# Doppler_LED_Controller.net
KiCad netlist of a schematic drawn in EAGLE
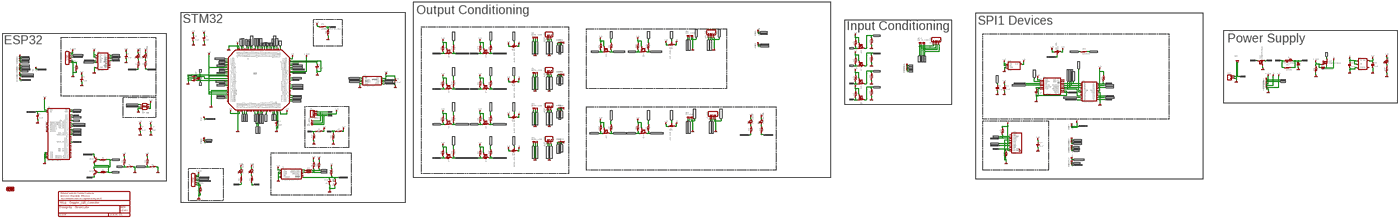
[diagram p0: schematic, sheet 1, overview]
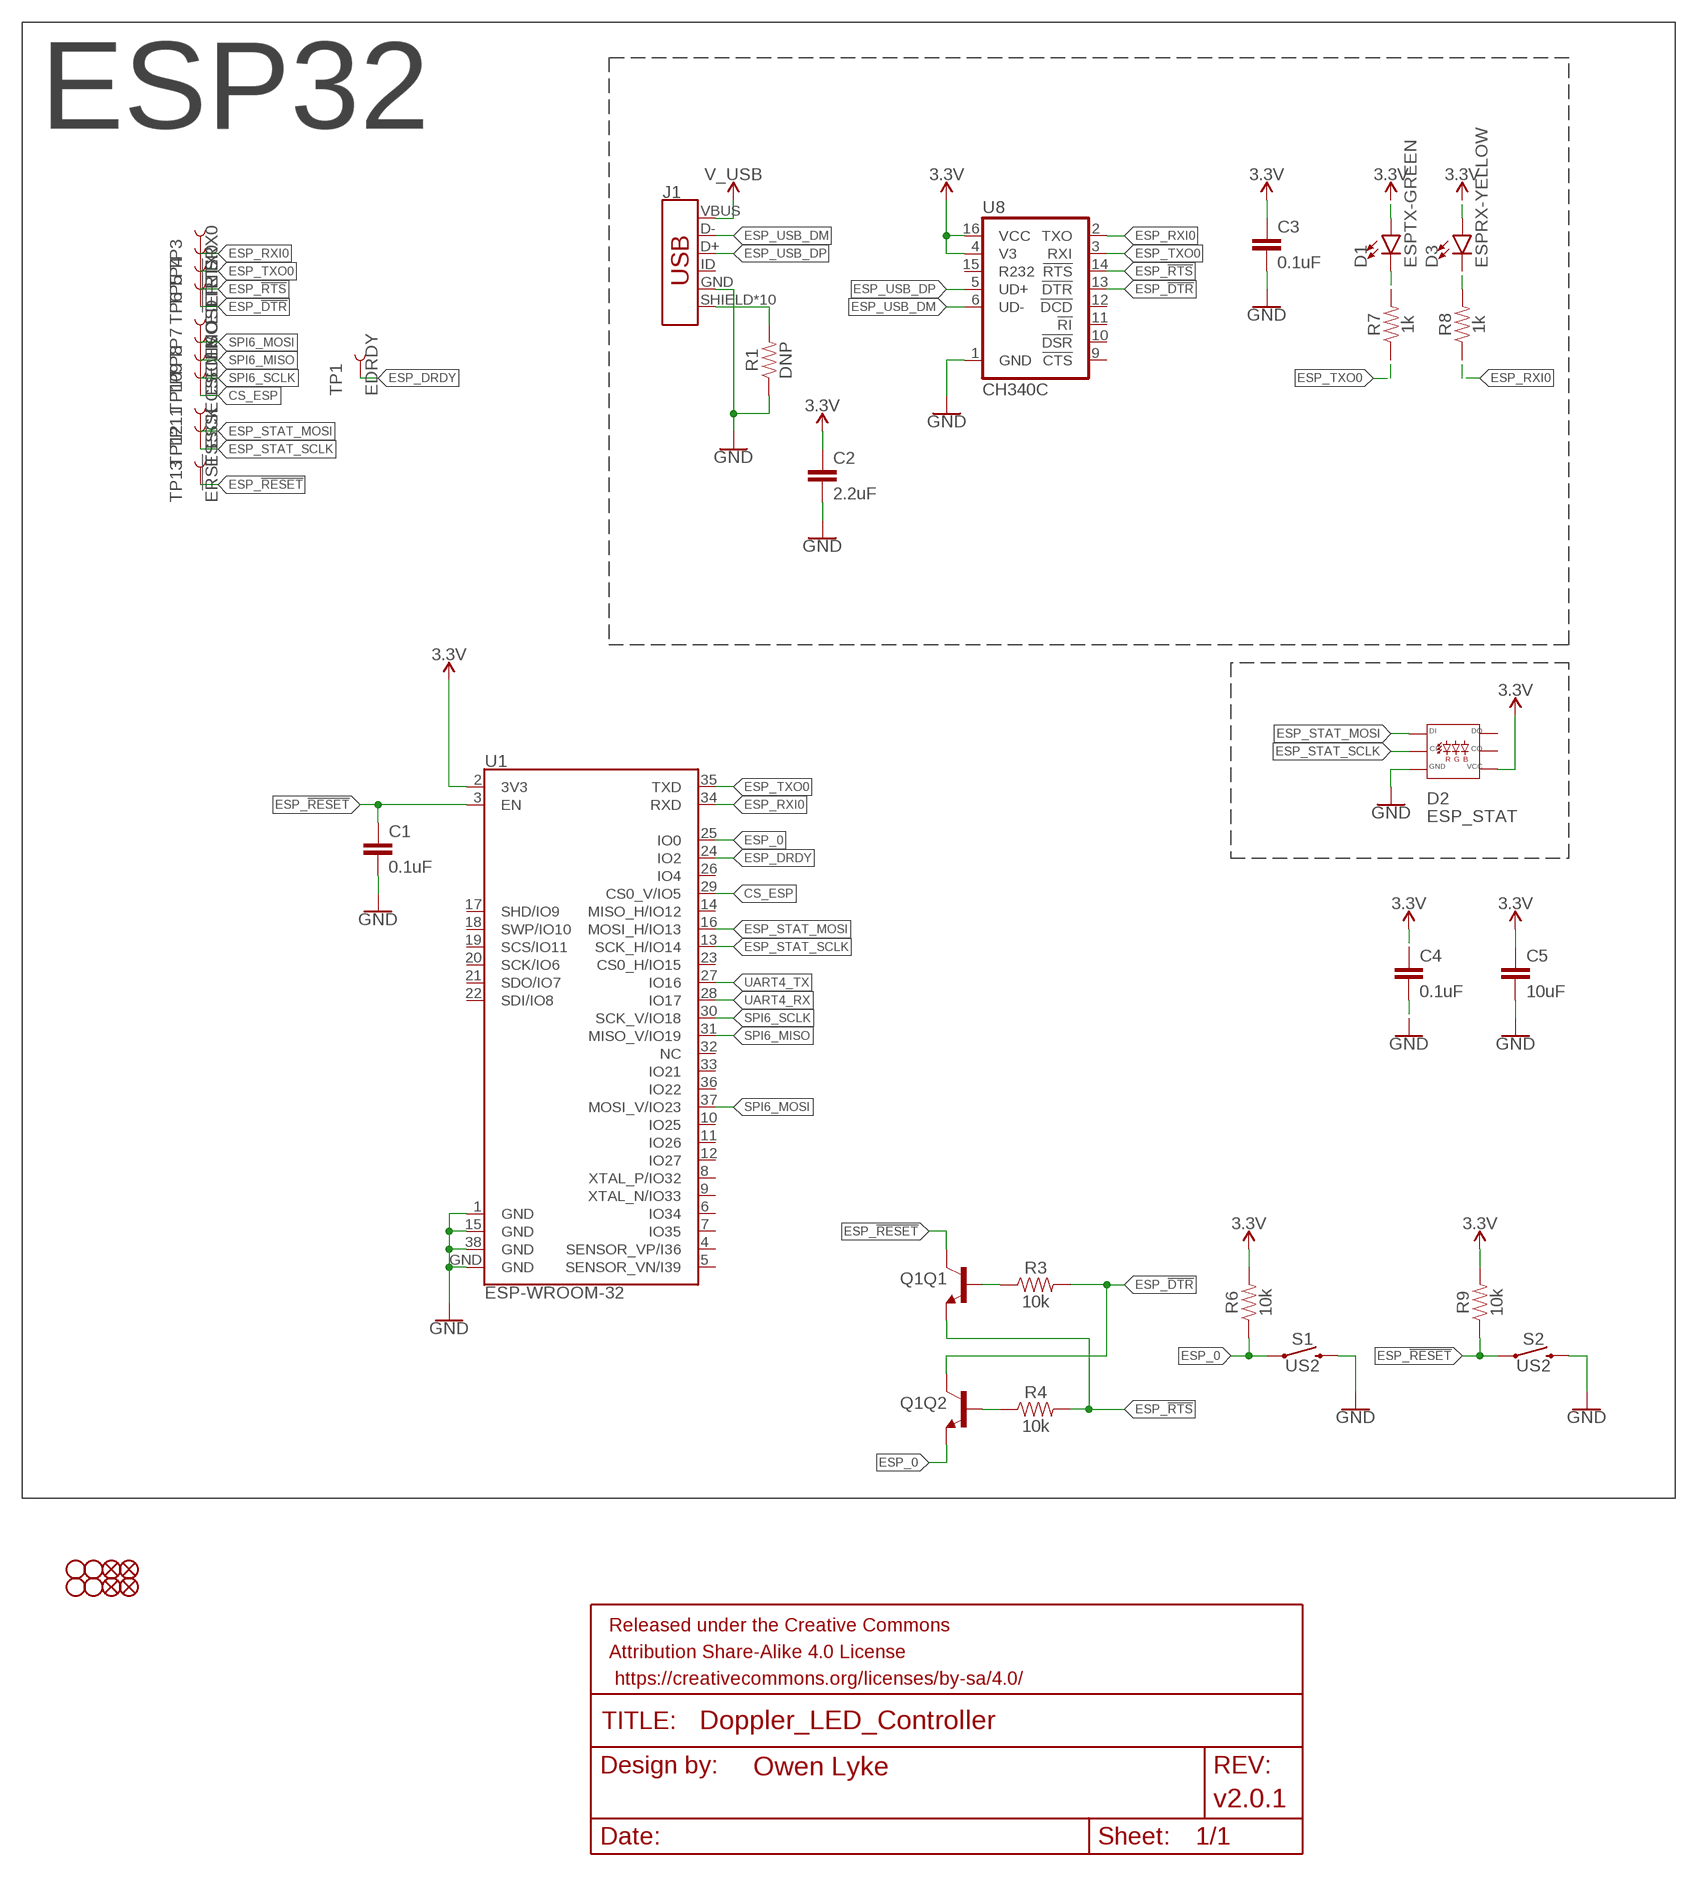
[diagram p1: schematic, sheet 1, part 1 of 6]
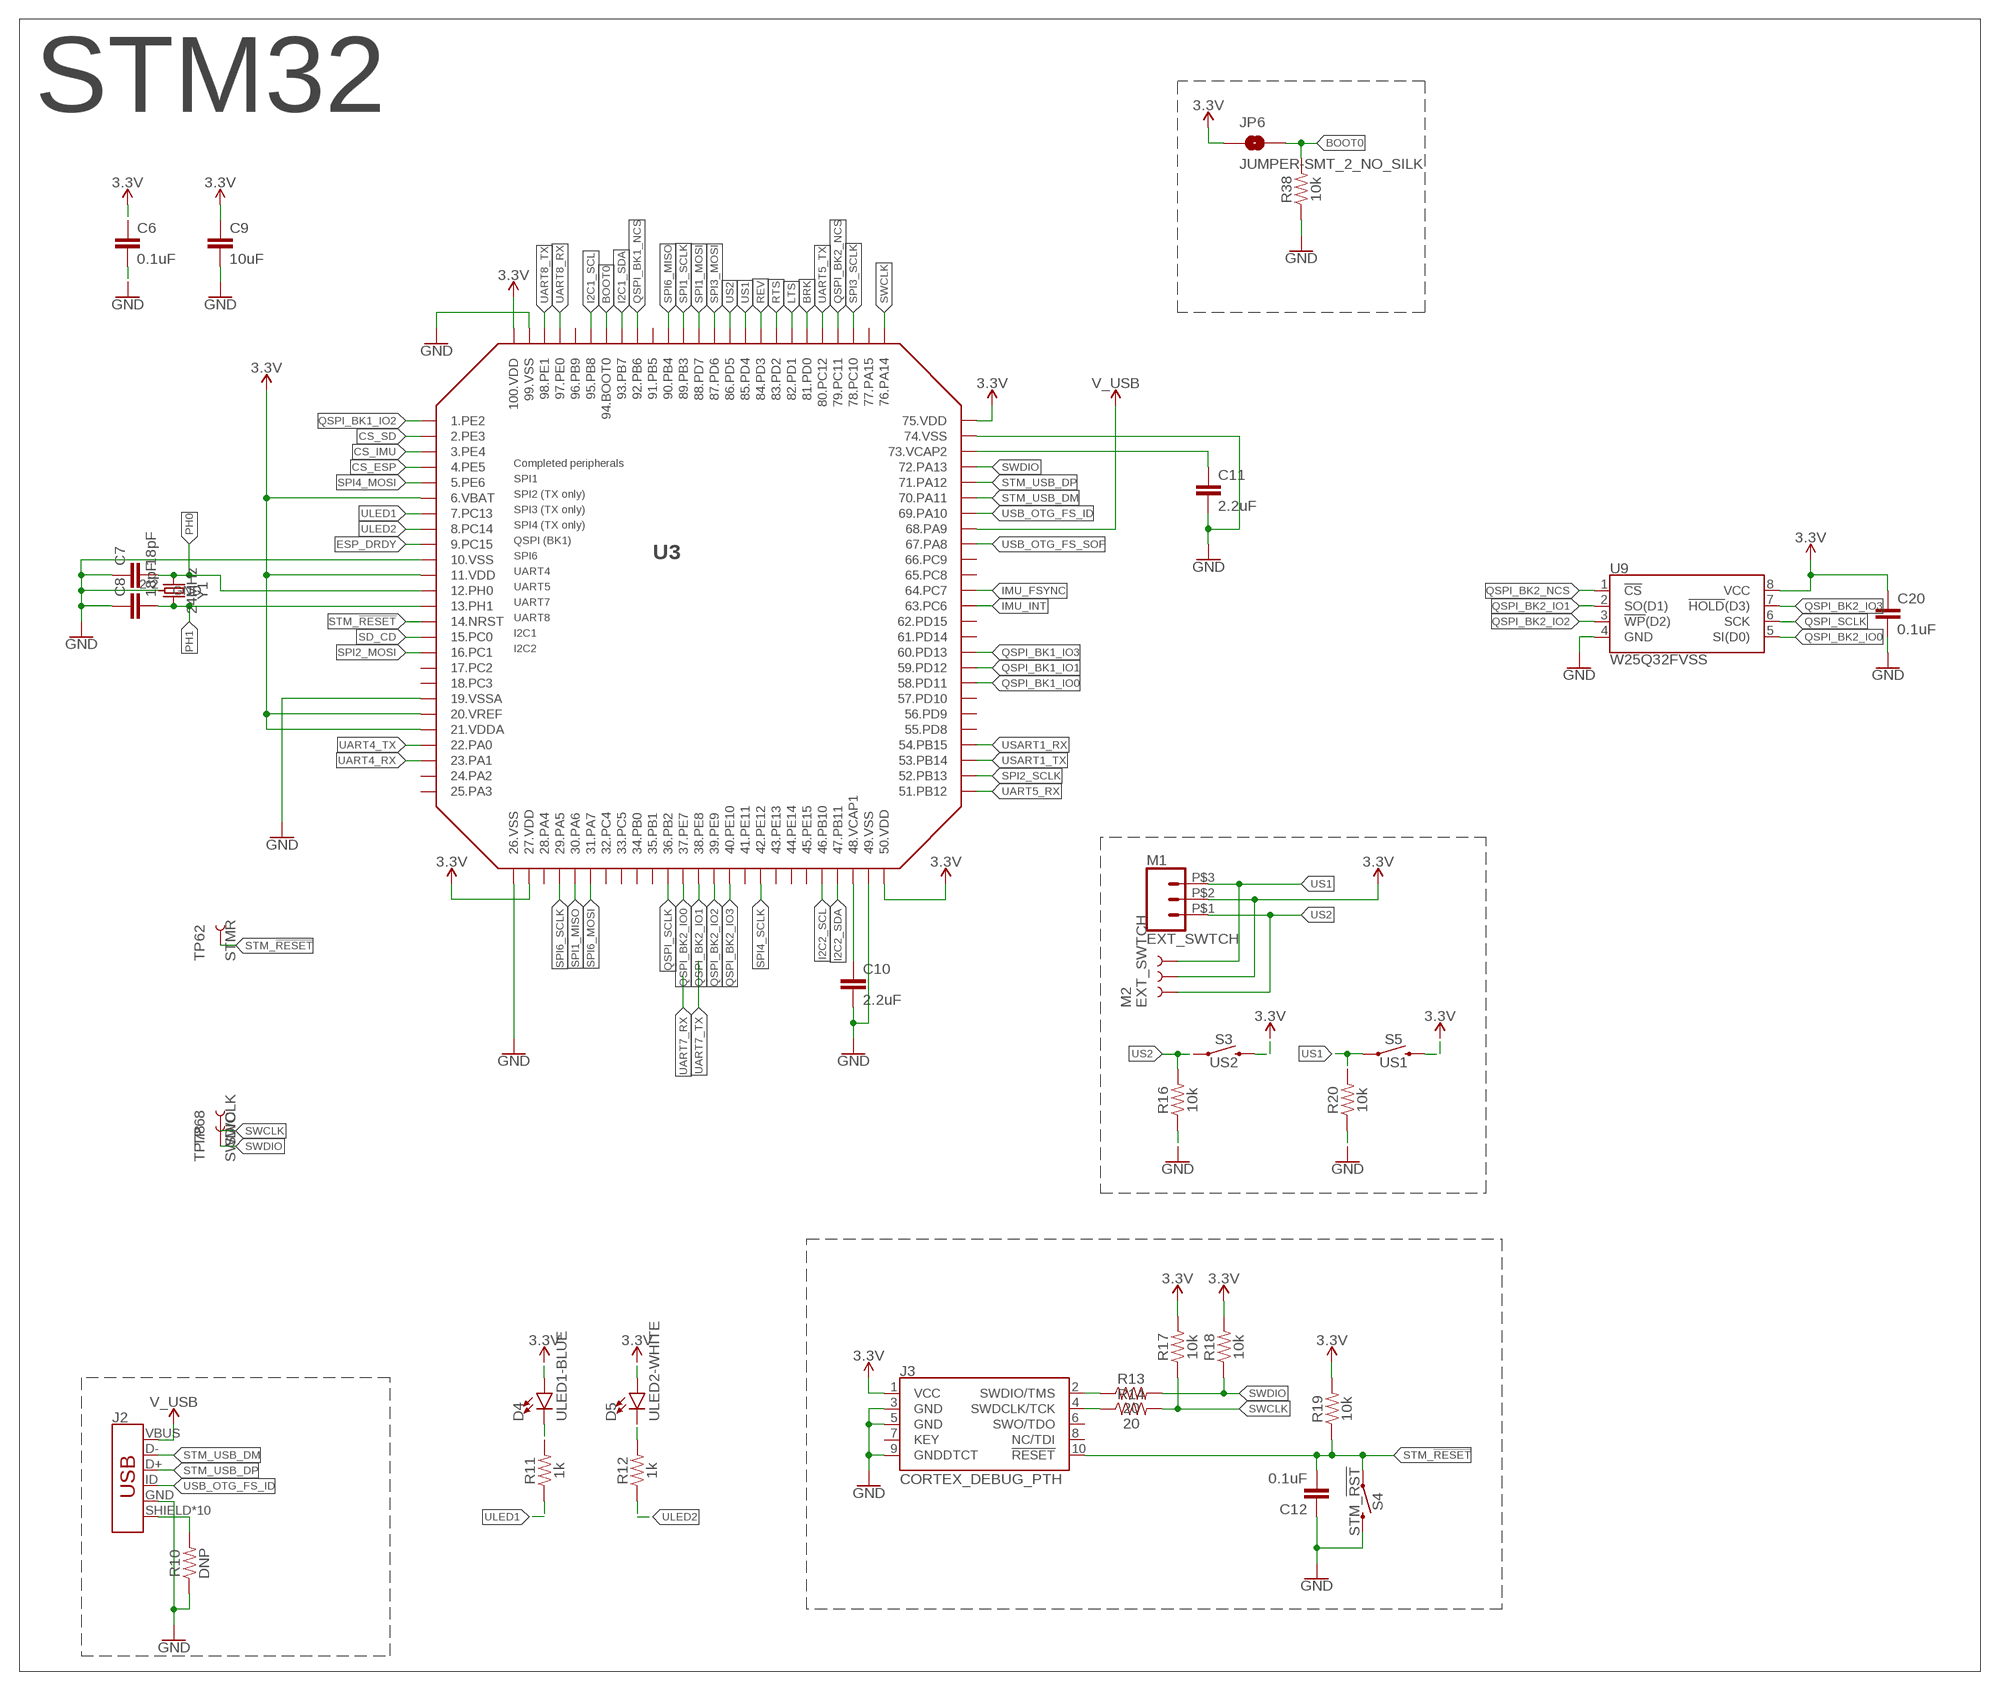
[diagram p2: schematic, sheet 1, part 2 of 6]
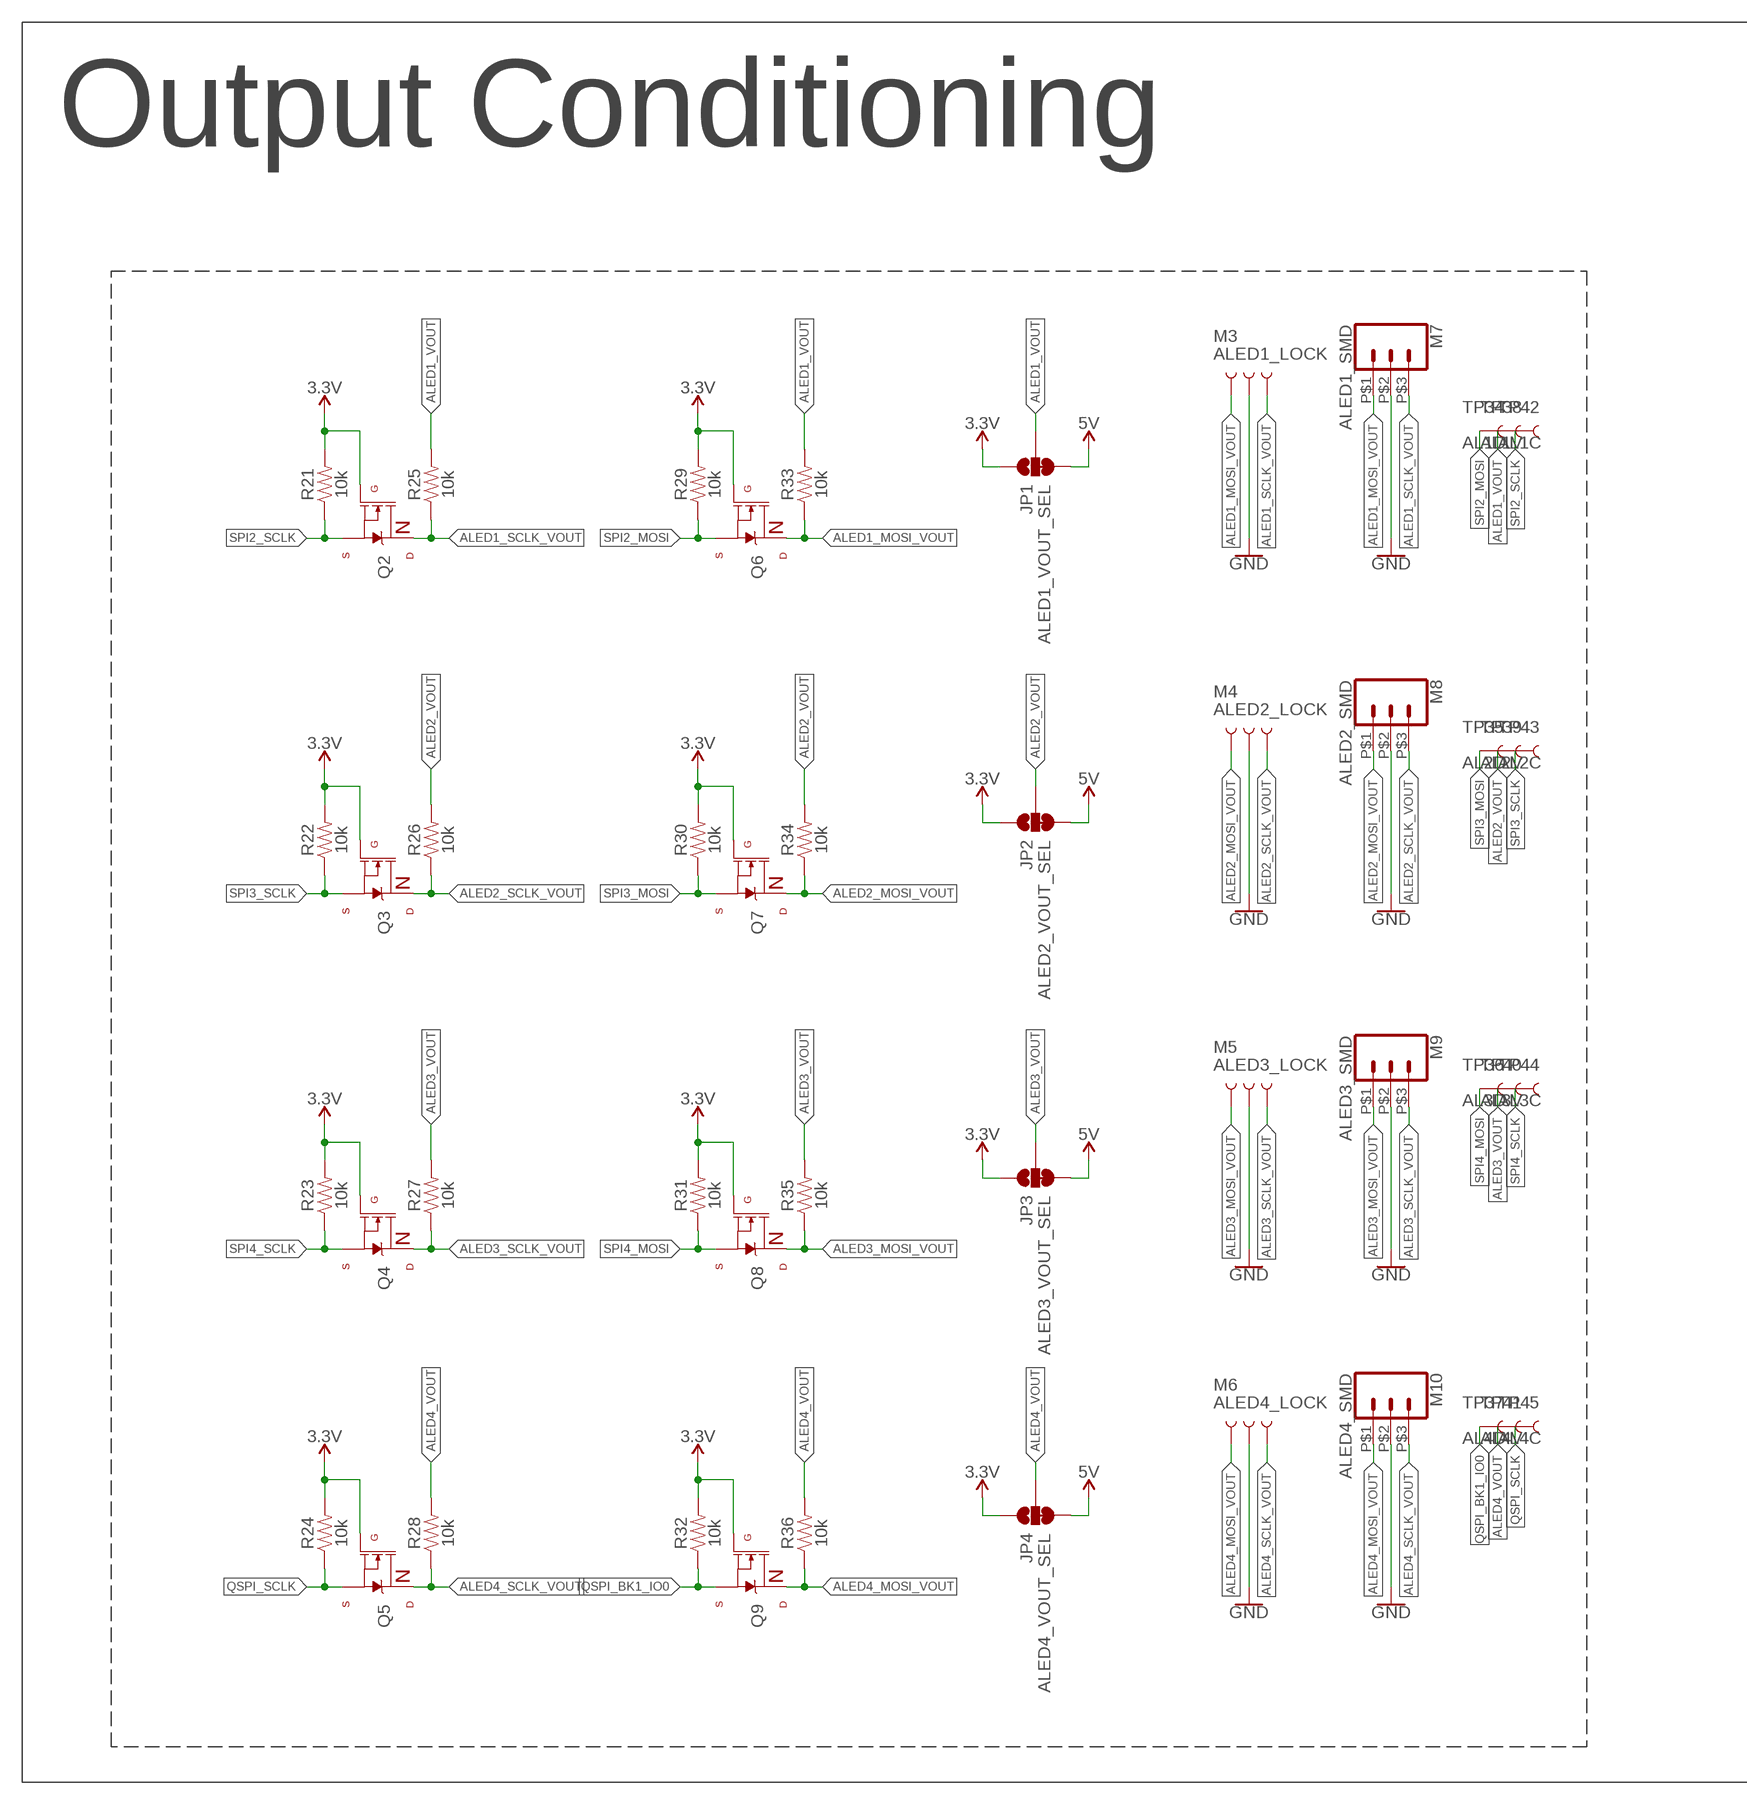
[diagram p3: schematic, sheet 1, part 3 of 6]
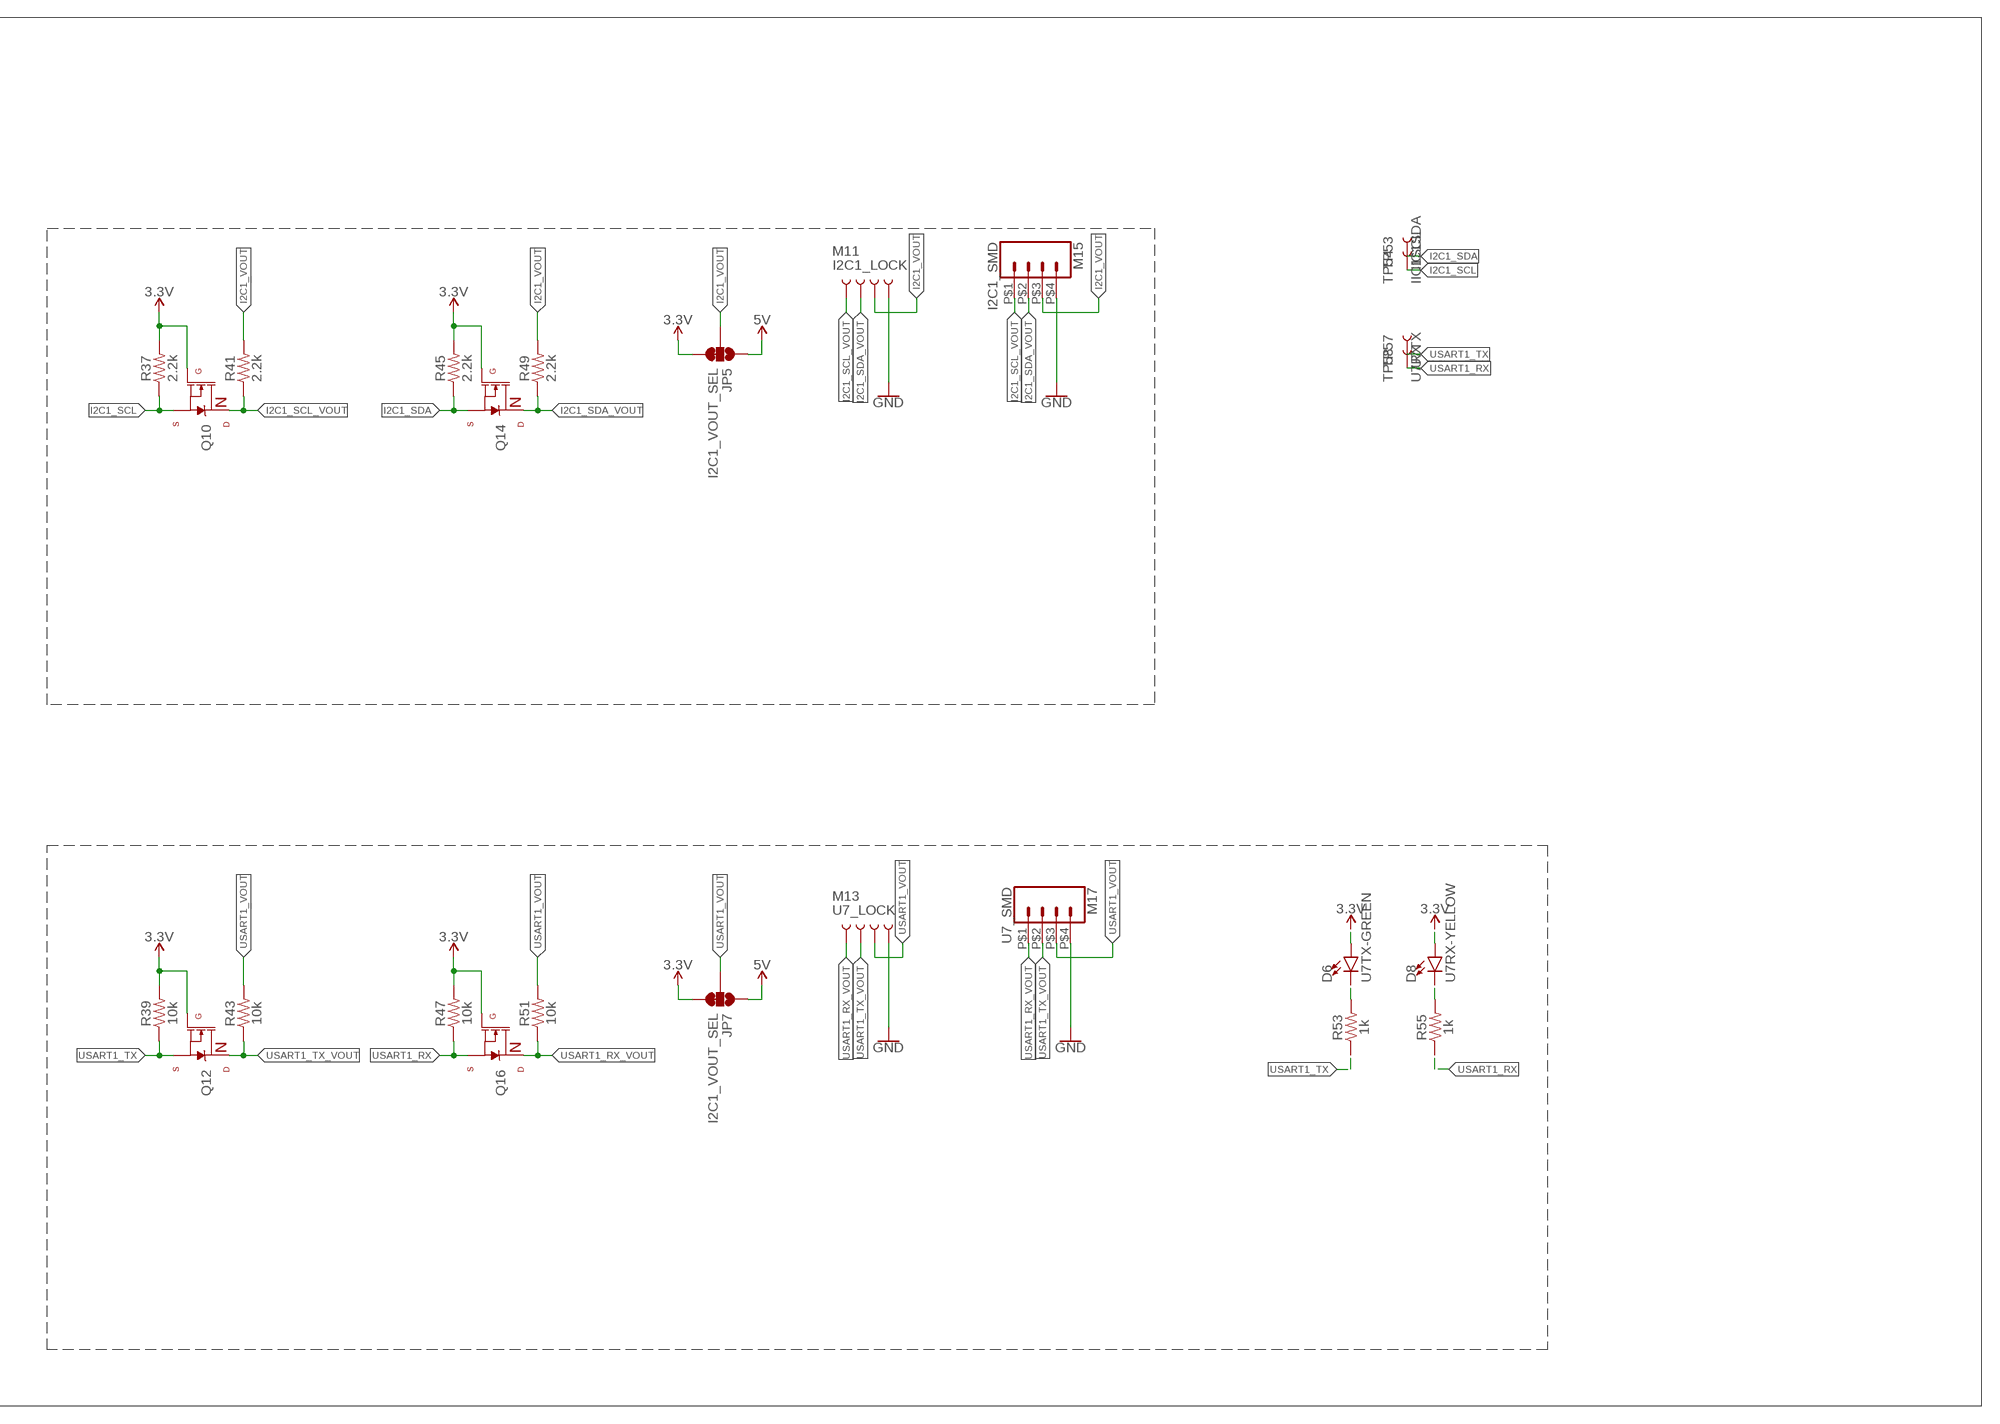
[diagram p4: schematic, sheet 1, part 4 of 6]
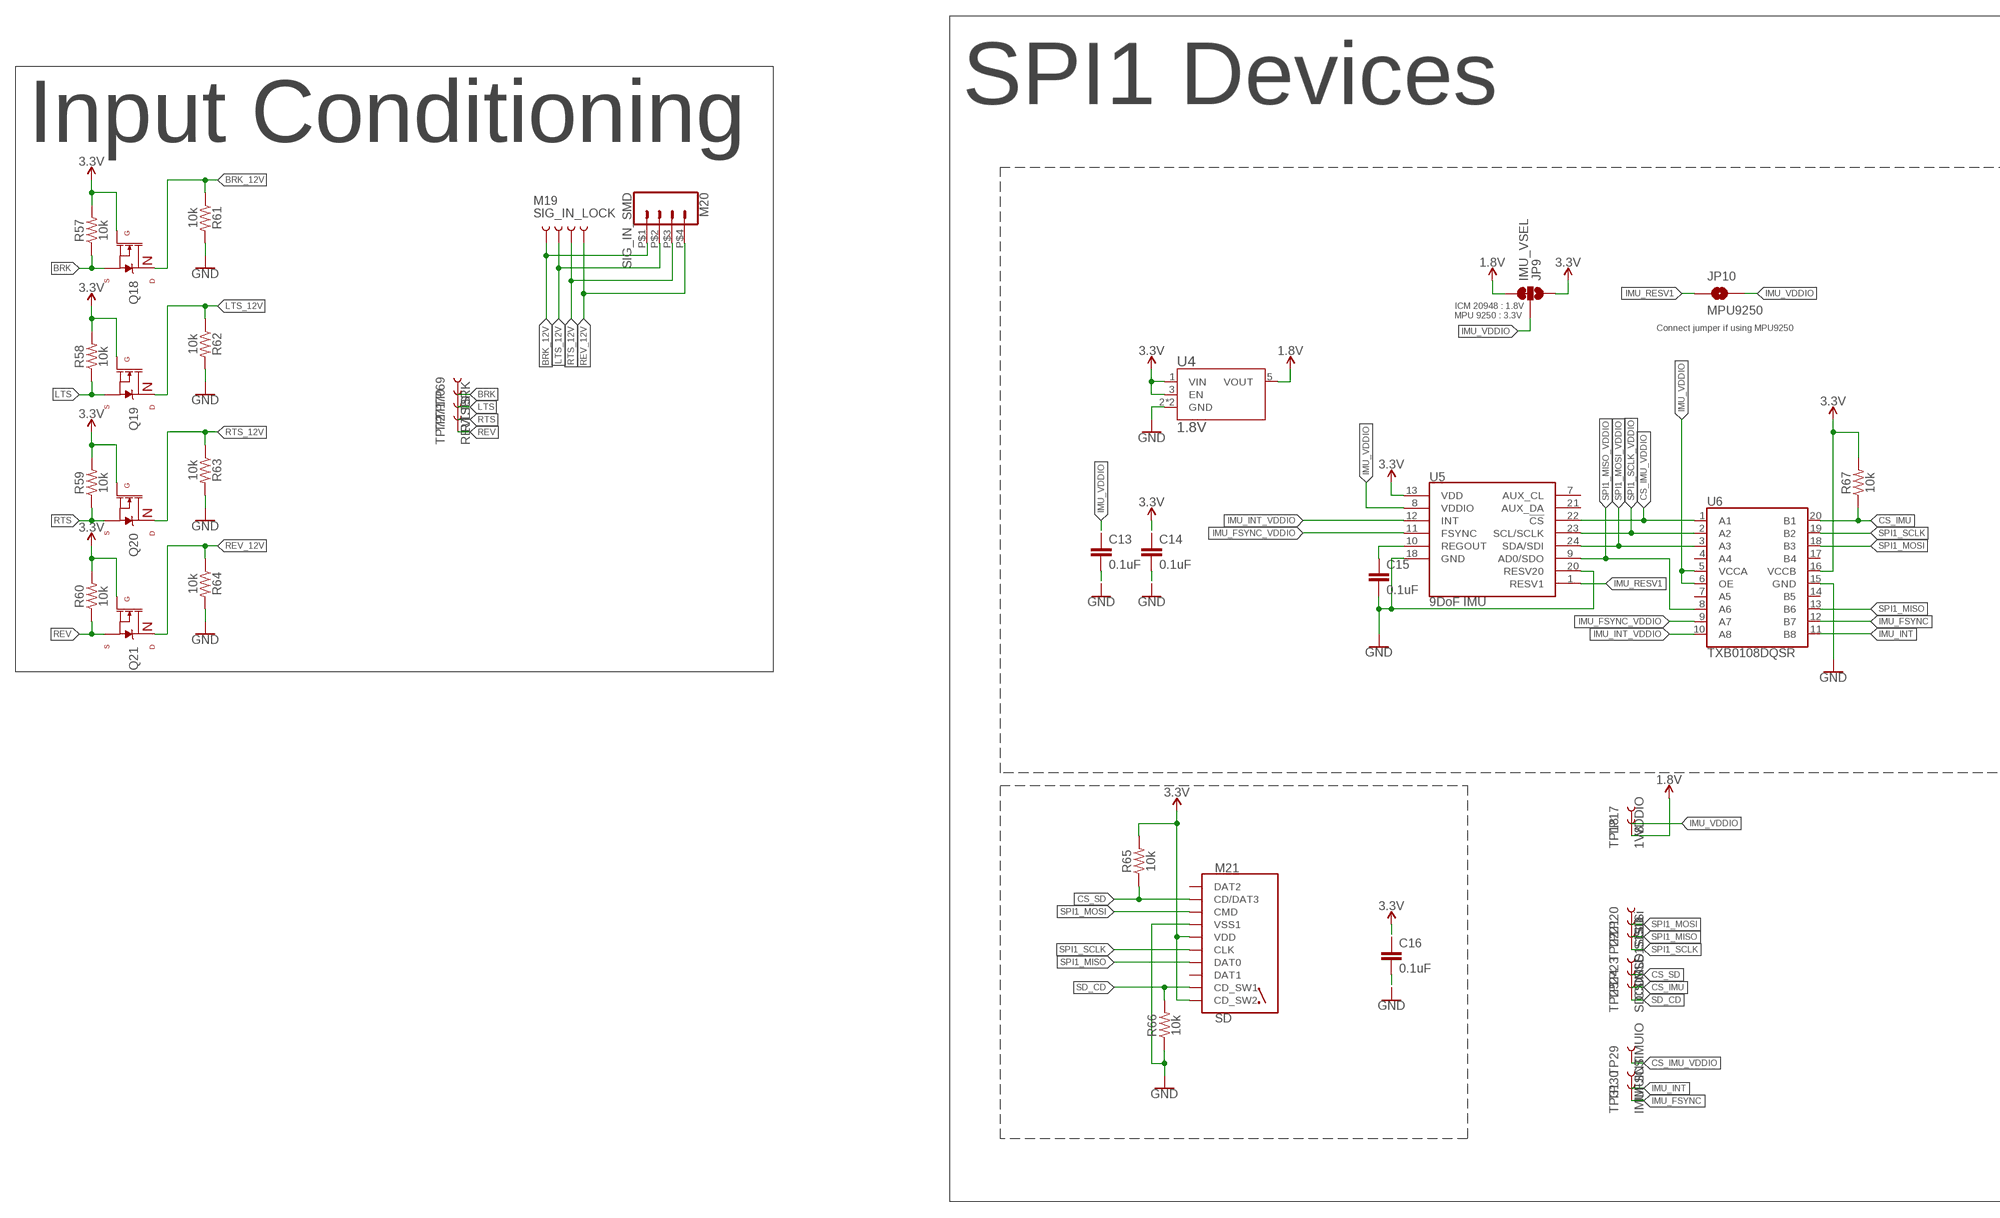
[diagram p5: schematic, sheet 1, part 5 of 6]
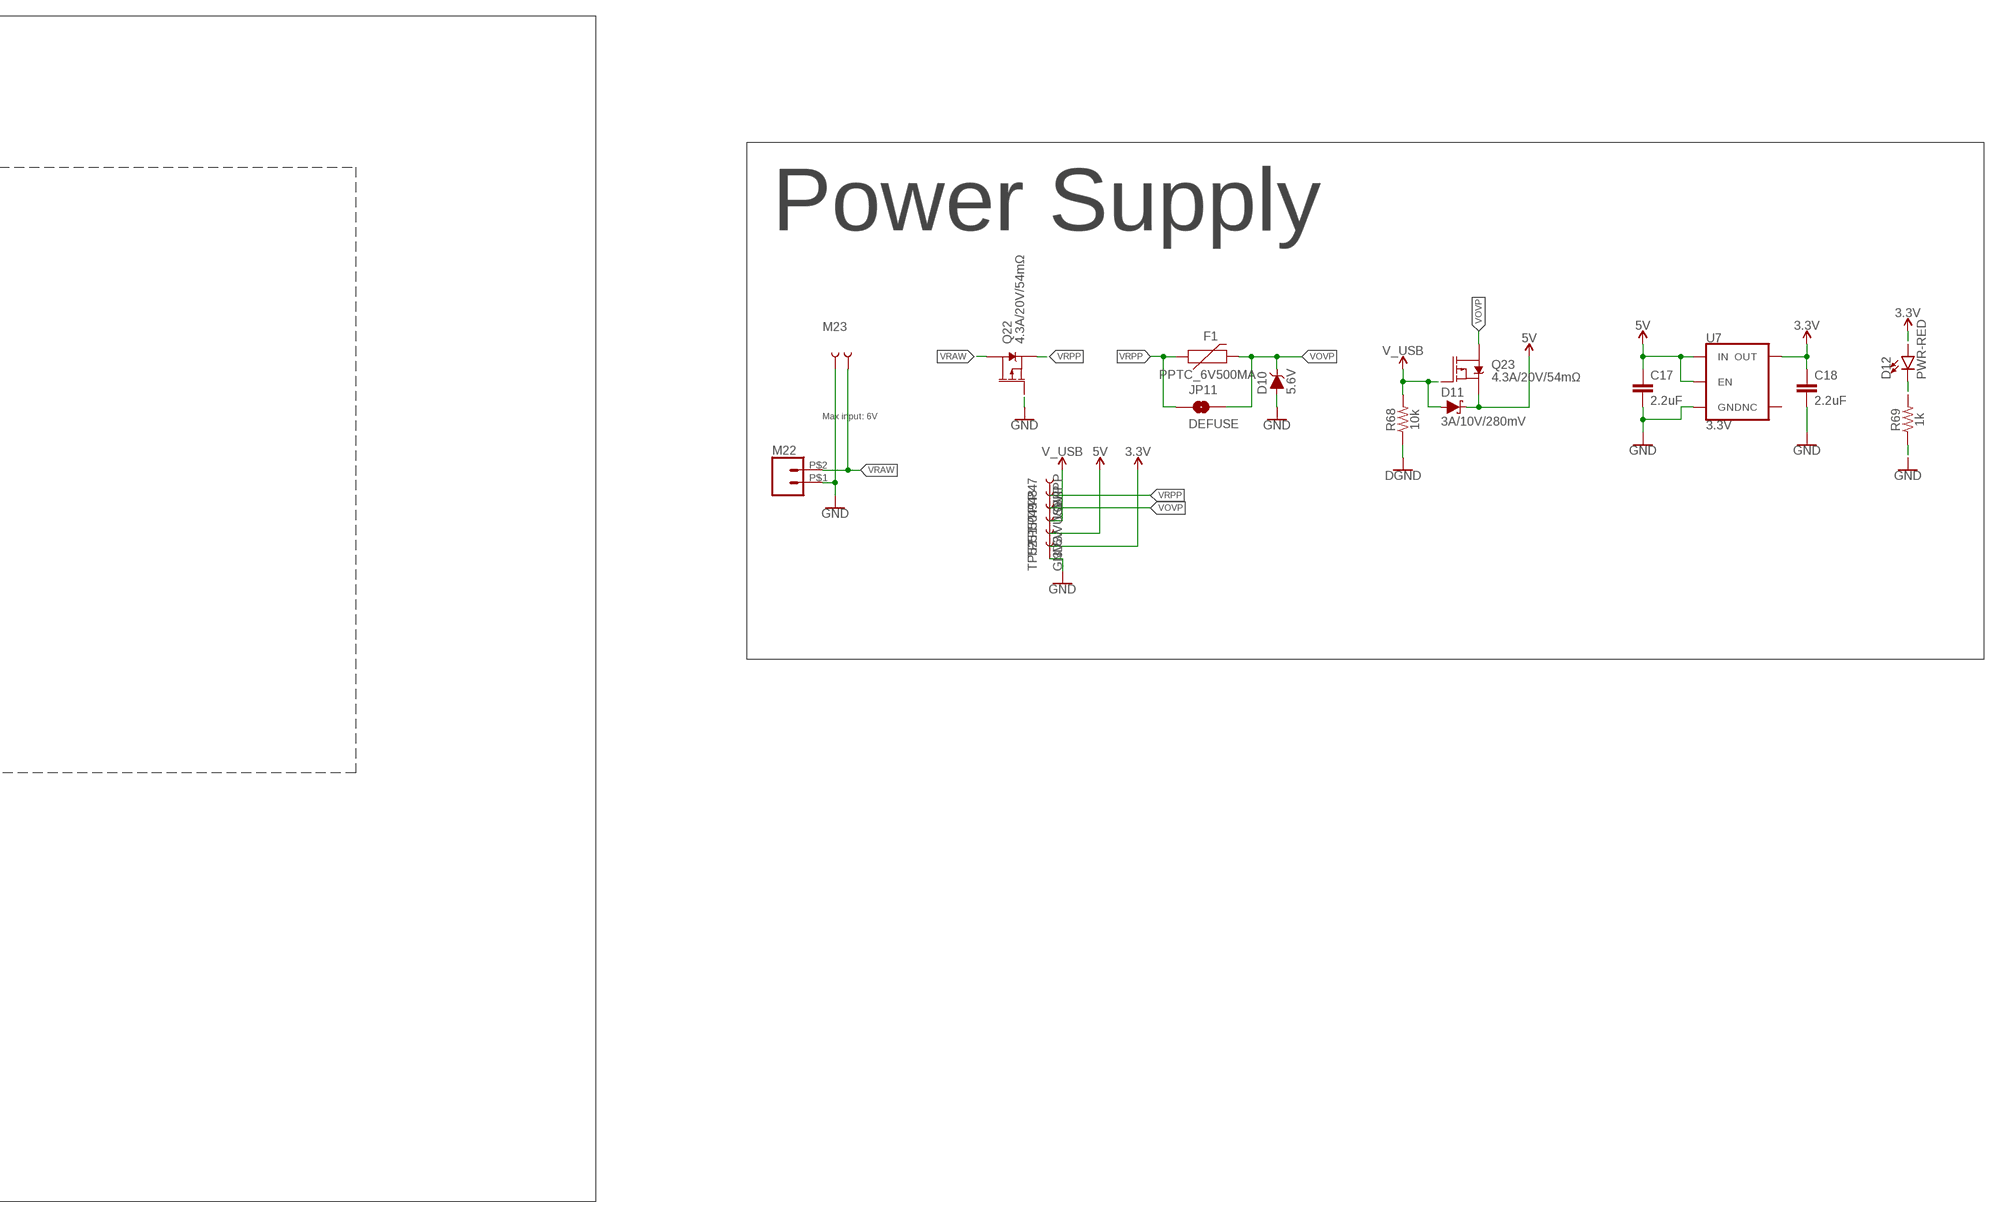
[diagram p6: schematic, sheet 1, part 6 of 6]

(export (version "E")
  (design (tool "Eeschema 10.0.6"))
  (components
    (comp (ref "C1")
      (value "0.1uF")
      (footprint "eagle-import:0603")
      (libsource (lib "eagle-import") (part "0.1UF-0603-25V-5%"))
    )
    (comp (ref "C2")
      (value "2.2uF")
      (footprint "eagle-import:0603")
      (libsource (lib "eagle-import") (part "2.2UF-0603-10V-20%"))
    )
    (comp (ref "C3")
      (value "0.1uF")
      (footprint "eagle-import:0603")
      (libsource (lib "eagle-import") (part "0.1UF-0603-25V-5%"))
    )
    (comp (ref "C4")
      (value "0.1uF")
      (footprint "eagle-import:0603")
      (libsource (lib "eagle-import") (part "0.1UF-0603-25V-5%"))
    )
    (comp (ref "C5")
      (value "10uF")
      (footprint "eagle-import:0603")
      (libsource (lib "eagle-import") (part "10UF-0603-6.3V-20%"))
    )
    (comp (ref "C6")
      (value "0.1uF")
      (footprint "eagle-import:0603")
      (libsource (lib "eagle-import") (part "0.1UF-0603-25V-5%"))
    )
    (comp (ref "C7")
      (value "18pF")
      (footprint "eagle-import:0603")
      (libsource (lib "eagle-import") (part "18PF-0603-50V-5%"))
    )
    (comp (ref "C8")
      (value "18pF")
      (footprint "eagle-import:0603")
      (libsource (lib "eagle-import") (part "18PF-0603-50V-5%"))
    )
    (comp (ref "C9")
      (value "10uF")
      (footprint "eagle-import:0603")
      (libsource (lib "eagle-import") (part "10UF-0603-6.3V-20%"))
    )
    (comp (ref "C10")
      (value "2.2uF")
      (footprint "eagle-import:0603")
      (libsource (lib "eagle-import") (part "2.2UF-0603-10V-20%"))
    )
    (comp (ref "C11")
      (value "2.2uF")
      (footprint "eagle-import:0603")
      (libsource (lib "eagle-import") (part "2.2UF-0603-10V-20%"))
    )
    (comp (ref "C12")
      (value "0.1uF")
      (footprint "eagle-import:0603")
      (libsource (lib "eagle-import") (part "0.1UF-0603-25V-5%"))
    )
    (comp (ref "C13")
      (value "0.1uF")
      (footprint "eagle-import:0603")
      (libsource (lib "eagle-import") (part "0.1UF-0603-25V-5%"))
    )
    (comp (ref "C14")
      (value "0.1uF")
      (footprint "eagle-import:0603")
      (libsource (lib "eagle-import") (part "0.1UF-0603-25V-5%"))
    )
    (comp (ref "C15")
      (value "0.1uF")
      (footprint "eagle-import:0603")
      (libsource (lib "eagle-import") (part "0.1UF-0603-25V-5%"))
    )
    (comp (ref "C16")
      (value "0.1uF")
      (footprint "eagle-import:0603")
      (libsource (lib "eagle-import") (part "0.1UF-0603-25V-5%"))
    )
    (comp (ref "C17")
      (value "2.2uF")
      (footprint "eagle-import:0603")
      (libsource (lib "eagle-import") (part "2.2UF-0603-10V-20%"))
    )
    (comp (ref "C18")
      (value "2.2uF")
      (footprint "eagle-import:0603")
      (libsource (lib "eagle-import") (part "2.2UF-0603-10V-20%"))
    )
    (comp (ref "C20")
      (value "0.1uF")
      (footprint "eagle-import:0603")
      (libsource (lib "eagle-import") (part "0.1UF-0603-25V-(+80/-20%)"))
    )
    (comp (ref "D1")
      (value "ESPTX-GREEN")
      (footprint "eagle-import:LED-0603")
      (libsource (lib "eagle-import") (part "LED-GREEN0603"))
    )
    (comp (ref "D2")
      (value "ESP_STAT")
      (footprint "eagle-import:APA102_2020_LONG")
      (libsource (lib "eagle-import") (part "APA1022020_LONG"))
    )
    (comp (ref "D3")
      (value "ESPRX-YELLOW")
      (footprint "eagle-import:LED-0603")
      (libsource (lib "eagle-import") (part "LED-YELLOW0603"))
    )
    (comp (ref "D4")
      (value "ULED1-BLUE")
      (footprint "eagle-import:LED-0603")
      (libsource (lib "eagle-import") (part "LED-BLUE0603"))
    )
    (comp (ref "D5")
      (value "ULED2-WHITE")
      (footprint "eagle-import:LED-0603")
      (libsource (lib "eagle-import") (part "LED-WHITE0603"))
    )
    (comp (ref "D6")
      (value "U7TX-GREEN")
      (footprint "eagle-import:LED-0603")
      (libsource (lib "eagle-import") (part "LED-GREEN0603"))
    )
    (comp (ref "D8")
      (value "U7RX-YELLOW")
      (footprint "eagle-import:LED-0603")
      (libsource (lib "eagle-import") (part "LED-YELLOW0603"))
    )
    (comp (ref "D10")
      (value "5.6V")
      (footprint "eagle-import:SOD-323")
      (libsource (lib "eagle-import") (part "DIODE-ZENER-MMSZ5232BS"))
    )
    (comp (ref "D11")
      (value "3A/10V/280mV")
      (footprint "eagle-import:SOD-323")
      (libsource (lib "eagle-import") (part "DIODE-SCHOTTKY-BAT60A"))
    )
    (comp (ref "D12")
      (value "PWR-RED")
      (footprint "eagle-import:LED-0603")
      (libsource (lib "eagle-import") (part "LED-RED0603"))
    )
    (comp (ref "F1")
      (value "PPTC_6V500MA")
      (footprint "eagle-import:0805")
      (libsource (lib "eagle-import") (part "PPTC_6V500MA"))
    )
    (comp (ref "FD1")
      (value "FIDUCIAL1X2")
      (footprint "eagle-import:FIDUCIAL-1X2")
      (libsource (lib "eagle-import") (part "FIDUCIAL1X2"))
    )
    (comp (ref "FD2")
      (value "FIDUCIAL1X2")
      (footprint "eagle-import:FIDUCIAL-1X2")
      (libsource (lib "eagle-import") (part "FIDUCIAL1X2"))
    )
    (comp (ref "FD3")
      (value "FIDUCIAL1X2")
      (footprint "eagle-import:FIDUCIAL-1X2")
      (libsource (lib "eagle-import") (part "FIDUCIAL1X2"))
    )
    (comp (ref "FD4")
      (value "FIDUCIAL1X2")
      (footprint "eagle-import:FIDUCIAL-1X2")
      (libsource (lib "eagle-import") (part "FIDUCIAL1X2"))
    )
    (comp (ref "H1")
      (value "STAND-OFF")
      (footprint "eagle-import:STAND-OFF")
      (libsource (lib "eagle-import") (part "STAND-OFF"))
    )
    (comp (ref "H2")
      (value "STAND-OFF")
      (footprint "eagle-import:STAND-OFF")
      (libsource (lib "eagle-import") (part "STAND-OFF"))
    )
    (comp (ref "H3")
      (value "STAND-OFF")
      (footprint "eagle-import:STAND-OFF")
      (libsource (lib "eagle-import") (part "STAND-OFF"))
    )
    (comp (ref "H4")
      (value "STAND-OFF")
      (footprint "eagle-import:STAND-OFF")
      (libsource (lib "eagle-import") (part "STAND-OFF"))
    )
    (comp (ref "J1")
      (value "USB_MICRO-B_HALF_PTH_MILL")
      (footprint "eagle-import:USB-MICROB-PTH-MILL")
      (libsource (lib "eagle-import") (part "USB_MICRO-B_HALF_PTH_MILL"))
    )
    (comp (ref "J2")
      (value "USB_MICRO-B_HALF_PTH_MILL")
      (footprint "eagle-import:USB-MICROB-PTH-MILL")
      (libsource (lib "eagle-import") (part "USB_MICRO-B_HALF_PTH_MILL"))
    )
    (comp (ref "J3")
      (value "CORTEX_DEBUG_PTH")
      (footprint "eagle-import:2X5-PTH-1.27MM")
      (libsource (lib "eagle-import") (part "CORTEX_DEBUG_PTH"))
    )
    (comp (ref "JP1")
      (value "ALED1_VOUT_SEL")
      (footprint "eagle-import:SMT-JUMPER_3_1-NC_TRACE_SILK")
      (libsource (lib "eagle-import") (part "JUMPER-SMT_3_1-NC_TRACE_SILK"))
    )
    (comp (ref "JP2")
      (value "ALED2_VOUT_SEL")
      (footprint "eagle-import:SMT-JUMPER_3_1-NC_TRACE_SILK")
      (libsource (lib "eagle-import") (part "JUMPER-SMT_3_1-NC_TRACE_SILK"))
    )
    (comp (ref "JP3")
      (value "ALED3_VOUT_SEL")
      (footprint "eagle-import:SMT-JUMPER_3_1-NC_TRACE_SILK")
      (libsource (lib "eagle-import") (part "JUMPER-SMT_3_1-NC_TRACE_SILK"))
    )
    (comp (ref "JP4")
      (value "ALED4_VOUT_SEL")
      (footprint "eagle-import:SMT-JUMPER_3_1-NC_TRACE_SILK")
      (libsource (lib "eagle-import") (part "JUMPER-SMT_3_1-NC_TRACE_SILK"))
    )
    (comp (ref "JP5")
      (value "I2C1_VOUT_SEL")
      (footprint "eagle-import:SMT-JUMPER_3_1-NC_TRACE_SILK")
      (libsource (lib "eagle-import") (part "JUMPER-SMT_3_1-NC_TRACE_SILK"))
    )
    (comp (ref "JP6")
      (value "JUMPER-SMT_2_NO_SILK")
      (footprint "eagle-import:SMT-JUMPER_2_NO_SILK")
      (libsource (lib "eagle-import") (part "JUMPER-SMT_2_NO_SILK"))
    )
    (comp (ref "JP7")
      (value "I2C1_VOUT_SEL")
      (footprint "eagle-import:SMT-JUMPER_3_1-NC_TRACE_SILK")
      (libsource (lib "eagle-import") (part "JUMPER-SMT_3_1-NC_TRACE_SILK"))
    )
    (comp (ref "JP9")
      (value "IMU_VSEL")
      (footprint "eagle-import:SMT-JUMPER_3_1-NC_TRACE_SILK")
      (libsource (lib "eagle-import") (part "JUMPER-SMT_3_1-NC_TRACE_SILK"))
    )
    (comp (ref "JP10")
      (value "MPU9250")
      (footprint "eagle-import:SMT-JUMPER_2_NO_SILK")
      (libsource (lib "eagle-import") (part "JUMPER-SMT_2_NO_SILK"))
    )
    (comp (ref "JP11")
      (value "DEFUSE")
      (footprint "eagle-import:SMT-JUMPER_2_NO_SILK")
      (libsource (lib "eagle-import") (part "JUMPER-SMT_2_NO_SILK"))
    )
    (comp (ref "M1")
      (value "EXT_SWTCH")
      (footprint "eagle-import:1X03_SMD_0.1IN")
      (libsource (lib "eagle-import") (part "CONN_SMD_3"))
    )
    (comp (ref "M2")
      (value "EXT_SWTCH")
      (footprint "eagle-import:3_PIN_LOCK")
      (libsource (lib "eagle-import") (part "CONN_LED_OUT-MOLEX_5055670371"))
    )
    (comp (ref "M3")
      (value "ALED1_LOCK")
      (footprint "eagle-import:3_PIN_LOCK")
      (libsource (lib "eagle-import") (part "CONN_LED_OUT-MOLEX_5055670371"))
    )
    (comp (ref "M4")
      (value "ALED2_LOCK")
      (footprint "eagle-import:3_PIN_LOCK")
      (libsource (lib "eagle-import") (part "CONN_LED_OUT-MOLEX_5055670371"))
    )
    (comp (ref "M5")
      (value "ALED3_LOCK")
      (footprint "eagle-import:3_PIN_LOCK")
      (libsource (lib "eagle-import") (part "CONN_LED_OUT-MOLEX_5055670371"))
    )
    (comp (ref "M6")
      (value "ALED4_LOCK")
      (footprint "eagle-import:3_PIN_LOCK")
      (libsource (lib "eagle-import") (part "CONN_LED_OUT-MOLEX_5055670371"))
    )
    (comp (ref "M7")
      (value "ALED1_SMD")
      (footprint "eagle-import:1X03_SMD_0.1IN")
      (libsource (lib "eagle-import") (part "CONN_SMD_3"))
    )
    (comp (ref "M8")
      (value "ALED2_SMD")
      (footprint "eagle-import:1X03_SMD_0.1IN")
      (libsource (lib "eagle-import") (part "CONN_SMD_3"))
    )
    (comp (ref "M9")
      (value "ALED3_SMD")
      (footprint "eagle-import:1X03_SMD_0.1IN")
      (libsource (lib "eagle-import") (part "CONN_SMD_3"))
    )
    (comp (ref "M10")
      (value "ALED4_SMD")
      (footprint "eagle-import:1X03_SMD_0.1IN")
      (libsource (lib "eagle-import") (part "CONN_SMD_3"))
    )
    (comp (ref "M11")
      (value "I2C1_LOCK")
      (footprint "eagle-import:4_PIN_LOCK")
      (libsource (lib "eagle-import") (part "CONN_LOCK_4-MOLEX_5055670471"))
    )
    (comp (ref "M13")
      (value "U7_LOCK")
      (footprint "eagle-import:4_PIN_LOCK")
      (libsource (lib "eagle-import") (part "CONN_LOCK_4-MOLEX_5055670471"))
    )
    (comp (ref "M15")
      (value "I2C1_SMD")
      (footprint "eagle-import:1X04_SMD_0.1IN")
      (libsource (lib "eagle-import") (part "CONN_SMD_4"))
    )
    (comp (ref "M17")
      (value "U7_SMD")
      (footprint "eagle-import:1X04_SMD_0.1IN")
      (libsource (lib "eagle-import") (part "CONN_SMD_4"))
    )
    (comp (ref "M19")
      (value "SIG_IN_LOCK")
      (footprint "eagle-import:4_PIN_LOCK")
      (libsource (lib "eagle-import") (part "CONN_LOCK_4-MOLEX_5055670471"))
    )
    (comp (ref "M20")
      (value "SIG_IN_SMD")
      (footprint "eagle-import:1X04_SMD_0.1IN")
      (libsource (lib "eagle-import") (part "CONN_SMD_4"))
    )
    (comp (ref "M21")
      (value "SD")
      (footprint "eagle-import:SD_AMPHENOL_PUSH_PULL")
      (libsource (lib "eagle-import") (part "SD_MICRO_SOCKET-114-00841-68"))
    )
    (comp (ref "M22")
      (value "CONN_SMD_2")
      (footprint "eagle-import:1X02_SMD_0.1IN")
      (libsource (lib "eagle-import") (part "CONN_SMD_2"))
    )
    (comp (ref "M23")
      (value "CONN_LOCK_2-5055670271")
      (footprint "eagle-import:2_PIN_LOCK")
      (libsource (lib "eagle-import") (part "CONN_LOCK_2-5055670271"))
    )
    (comp (ref "Q1")
      (value "TRANS_NPN_DUAL-MBT3904DW1T1")
      (footprint "eagle-import:SC70-6")
      (libsource (lib "eagle-import") (part "TRANS_NPN_DUAL-MBT3904DW1T1"))
    )
    (comp (ref "Q2")
      (value "AMP_MOSFET_NCH-2N7002K")
      (footprint "eagle-import:SOT23-3")
      (libsource (lib "eagle-import") (part "AMP_MOSFET_NCH-2N7002K"))
    )
    (comp (ref "Q3")
      (value "AMP_MOSFET_NCH-2N7002K")
      (footprint "eagle-import:SOT23-3")
      (libsource (lib "eagle-import") (part "AMP_MOSFET_NCH-2N7002K"))
    )
    (comp (ref "Q4")
      (value "AMP_MOSFET_NCH-2N7002K")
      (footprint "eagle-import:SOT23-3")
      (libsource (lib "eagle-import") (part "AMP_MOSFET_NCH-2N7002K"))
    )
    (comp (ref "Q5")
      (value "AMP_MOSFET_NCH-2N7002K")
      (footprint "eagle-import:SOT23-3")
      (libsource (lib "eagle-import") (part "AMP_MOSFET_NCH-2N7002K"))
    )
    (comp (ref "Q6")
      (value "AMP_MOSFET_NCH-2N7002K")
      (footprint "eagle-import:SOT23-3")
      (libsource (lib "eagle-import") (part "AMP_MOSFET_NCH-2N7002K"))
    )
    (comp (ref "Q7")
      (value "AMP_MOSFET_NCH-2N7002K")
      (footprint "eagle-import:SOT23-3")
      (libsource (lib "eagle-import") (part "AMP_MOSFET_NCH-2N7002K"))
    )
    (comp (ref "Q8")
      (value "AMP_MOSFET_NCH-2N7002K")
      (footprint "eagle-import:SOT23-3")
      (libsource (lib "eagle-import") (part "AMP_MOSFET_NCH-2N7002K"))
    )
    (comp (ref "Q9")
      (value "AMP_MOSFET_NCH-2N7002K")
      (footprint "eagle-import:SOT23-3")
      (libsource (lib "eagle-import") (part "AMP_MOSFET_NCH-2N7002K"))
    )
    (comp (ref "Q10")
      (value "AMP_MOSFET_NCH-2N7002K")
      (footprint "eagle-import:SOT23-3")
      (libsource (lib "eagle-import") (part "AMP_MOSFET_NCH-2N7002K"))
    )
    (comp (ref "Q12")
      (value "AMP_MOSFET_NCH-2N7002K")
      (footprint "eagle-import:SOT23-3")
      (libsource (lib "eagle-import") (part "AMP_MOSFET_NCH-2N7002K"))
    )
    (comp (ref "Q14")
      (value "AMP_MOSFET_NCH-2N7002K")
      (footprint "eagle-import:SOT23-3")
      (libsource (lib "eagle-import") (part "AMP_MOSFET_NCH-2N7002K"))
    )
    (comp (ref "Q16")
      (value "AMP_MOSFET_NCH-2N7002K")
      (footprint "eagle-import:SOT23-3")
      (libsource (lib "eagle-import") (part "AMP_MOSFET_NCH-2N7002K"))
    )
    (comp (ref "Q18")
      (value "AMP_MOSFET_NCH-2N7002K")
      (footprint "eagle-import:SOT23-3")
      (libsource (lib "eagle-import") (part "AMP_MOSFET_NCH-2N7002K"))
    )
    (comp (ref "Q19")
      (value "AMP_MOSFET_NCH-2N7002K")
      (footprint "eagle-import:SOT23-3")
      (libsource (lib "eagle-import") (part "AMP_MOSFET_NCH-2N7002K"))
    )
    (comp (ref "Q20")
      (value "AMP_MOSFET_NCH-2N7002K")
      (footprint "eagle-import:SOT23-3")
      (libsource (lib "eagle-import") (part "AMP_MOSFET_NCH-2N7002K"))
    )
    (comp (ref "Q21")
      (value "AMP_MOSFET_NCH-2N7002K")
      (footprint "eagle-import:SOT23-3")
      (libsource (lib "eagle-import") (part "AMP_MOSFET_NCH-2N7002K"))
    )
    (comp (ref "Q22")
      (value "4.3A/20V/54mΩ")
      (footprint "eagle-import:SOT23-3")
      (libsource (lib "eagle-import") (part "MOSFET_PCH-IRLML2244"))
    )
    (comp (ref "Q23")
      (value "4.3A/20V/54mΩ")
      (footprint "eagle-import:SOT23-3")
      (libsource (lib "eagle-import") (part "MOSFET_PCH-IRLML2244"))
    )
    (comp (ref "R1")
      (value "DNP")
      (footprint "eagle-import:0603")
      (libsource (lib "eagle-import") (part "1MOHM-0603-1/4W-5%"))
    )
    (comp (ref "R3")
      (value "10k")
      (footprint "eagle-import:0603")
      (libsource (lib "eagle-import") (part "10KOHM-0603-1/10W-1%"))
    )
    (comp (ref "R4")
      (value "10k")
      (footprint "eagle-import:0603")
      (libsource (lib "eagle-import") (part "10KOHM-0603-1/10W-1%"))
    )
    (comp (ref "R6")
      (value "10k")
      (footprint "eagle-import:0603")
      (libsource (lib "eagle-import") (part "10KOHM-0603-1/10W-1%"))
    )
    (comp (ref "R7")
      (value "1k")
      (footprint "eagle-import:0603")
      (libsource (lib "eagle-import") (part "1KOHM-0603-1/10W-1%"))
    )
    (comp (ref "R8")
      (value "1k")
      (footprint "eagle-import:0603")
      (libsource (lib "eagle-import") (part "1KOHM-0603-1/10W-1%"))
    )
    (comp (ref "R9")
      (value "10k")
      (footprint "eagle-import:0603")
      (libsource (lib "eagle-import") (part "10KOHM-0603-1/10W-1%"))
    )
    (comp (ref "R10")
      (value "DNP")
      (footprint "eagle-import:0603")
      (libsource (lib "eagle-import") (part "1MOHM-0603-1/4W-5%"))
    )
    (comp (ref "R11")
      (value "1k")
      (footprint "eagle-import:0603")
      (libsource (lib "eagle-import") (part "1KOHM-0603-1/10W-1%"))
    )
    (comp (ref "R12")
      (value "1k")
      (footprint "eagle-import:0603")
      (libsource (lib "eagle-import") (part "1KOHM-0603-1/10W-1%"))
    )
    (comp (ref "R13")
      (value "20")
      (footprint "eagle-import:0603")
      (libsource (lib "eagle-import") (part "20OHM-0603-1/10W-1%"))
    )
    (comp (ref "R14")
      (value "20")
      (footprint "eagle-import:0603")
      (libsource (lib "eagle-import") (part "20OHM-0603-1/10W-1%"))
    )
    (comp (ref "R16")
      (value "10k")
      (footprint "eagle-import:0603")
      (libsource (lib "eagle-import") (part "10KOHM-0603-1/10W-1%"))
    )
    (comp (ref "R17")
      (value "10k")
      (footprint "eagle-import:0603")
      (libsource (lib "eagle-import") (part "10KOHM-0603-1/10W-1%"))
    )
    (comp (ref "R18")
      (value "10k")
      (footprint "eagle-import:0603")
      (libsource (lib "eagle-import") (part "10KOHM-0603-1/10W-1%"))
    )
    (comp (ref "R19")
      (value "10k")
      (footprint "eagle-import:0603")
      (libsource (lib "eagle-import") (part "10KOHM-0603-1/10W-1%"))
    )
    (comp (ref "R20")
      (value "10k")
      (footprint "eagle-import:0603")
      (libsource (lib "eagle-import") (part "10KOHM-0603-1/10W-1%"))
    )
    (comp (ref "R21")
      (value "10k")
      (footprint "eagle-import:0603")
      (libsource (lib "eagle-import") (part "10KOHM-0603-1/10W-1%"))
    )
    (comp (ref "R22")
      (value "10k")
      (footprint "eagle-import:0603")
      (libsource (lib "eagle-import") (part "10KOHM-0603-1/10W-1%"))
    )
    (comp (ref "R23")
      (value "10k")
      (footprint "eagle-import:0603")
      (libsource (lib "eagle-import") (part "10KOHM-0603-1/10W-1%"))
    )
    (comp (ref "R24")
      (value "10k")
      (footprint "eagle-import:0603")
      (libsource (lib "eagle-import") (part "10KOHM-0603-1/10W-1%"))
    )
    (comp (ref "R25")
      (value "10k")
      (footprint "eagle-import:0603")
      (libsource (lib "eagle-import") (part "10KOHM-0603-1/10W-1%"))
    )
    (comp (ref "R26")
      (value "10k")
      (footprint "eagle-import:0603")
      (libsource (lib "eagle-import") (part "10KOHM-0603-1/10W-1%"))
    )
    (comp (ref "R27")
      (value "10k")
      (footprint "eagle-import:0603")
      (libsource (lib "eagle-import") (part "10KOHM-0603-1/10W-1%"))
    )
    (comp (ref "R28")
      (value "10k")
      (footprint "eagle-import:0603")
      (libsource (lib "eagle-import") (part "10KOHM-0603-1/10W-1%"))
    )
    (comp (ref "R29")
      (value "10k")
      (footprint "eagle-import:0603")
      (libsource (lib "eagle-import") (part "10KOHM-0603-1/10W-1%"))
    )
    (comp (ref "R30")
      (value "10k")
      (footprint "eagle-import:0603")
      (libsource (lib "eagle-import") (part "10KOHM-0603-1/10W-1%"))
    )
    (comp (ref "R31")
      (value "10k")
      (footprint "eagle-import:0603")
      (libsource (lib "eagle-import") (part "10KOHM-0603-1/10W-1%"))
    )
    (comp (ref "R32")
      (value "10k")
      (footprint "eagle-import:0603")
      (libsource (lib "eagle-import") (part "10KOHM-0603-1/10W-1%"))
    )
    (comp (ref "R33")
      (value "10k")
      (footprint "eagle-import:0603")
      (libsource (lib "eagle-import") (part "10KOHM-0603-1/10W-1%"))
    )
    (comp (ref "R34")
      (value "10k")
      (footprint "eagle-import:0603")
      (libsource (lib "eagle-import") (part "10KOHM-0603-1/10W-1%"))
    )
    (comp (ref "R35")
      (value "10k")
      (footprint "eagle-import:0603")
      (libsource (lib "eagle-import") (part "10KOHM-0603-1/10W-1%"))
    )
    (comp (ref "R36")
      (value "10k")
      (footprint "eagle-import:0603")
      (libsource (lib "eagle-import") (part "10KOHM-0603-1/10W-1%"))
    )
    (comp (ref "R37")
      (value "2.2k")
      (footprint "eagle-import:0603")
      (libsource (lib "eagle-import") (part "2.2KOHM-0603-1/10W-1%"))
    )
    (comp (ref "R38")
      (value "10k")
      (footprint "eagle-import:0603")
      (libsource (lib "eagle-import") (part "10KOHM-0603-1/10W-1%"))
    )
    (comp (ref "R39")
      (value "10k")
      (footprint "eagle-import:0603")
      (libsource (lib "eagle-import") (part "10KOHM-0603-1/10W-1%"))
    )
    (comp (ref "R41")
      (value "2.2k")
      (footprint "eagle-import:0603")
      (libsource (lib "eagle-import") (part "2.2KOHM-0603-1/10W-1%"))
    )
    (comp (ref "R43")
      (value "10k")
      (footprint "eagle-import:0603")
      (libsource (lib "eagle-import") (part "10KOHM-0603-1/10W-1%"))
    )
    (comp (ref "R45")
      (value "2.2k")
      (footprint "eagle-import:0603")
      (libsource (lib "eagle-import") (part "2.2KOHM-0603-1/10W-1%"))
    )
    (comp (ref "R47")
      (value "10k")
      (footprint "eagle-import:0603")
      (libsource (lib "eagle-import") (part "10KOHM-0603-1/10W-1%"))
    )
    (comp (ref "R49")
      (value "2.2k")
      (footprint "eagle-import:0603")
      (libsource (lib "eagle-import") (part "2.2KOHM-0603-1/10W-1%"))
    )
    (comp (ref "R51")
      (value "10k")
      (footprint "eagle-import:0603")
      (libsource (lib "eagle-import") (part "10KOHM-0603-1/10W-1%"))
    )
    (comp (ref "R53")
      (value "1k")
      (footprint "eagle-import:0603")
      (libsource (lib "eagle-import") (part "1KOHM-0603-1/10W-1%"))
    )
    (comp (ref "R55")
      (value "1k")
      (footprint "eagle-import:0603")
      (libsource (lib "eagle-import") (part "1KOHM-0603-1/10W-1%"))
    )
    (comp (ref "R57")
      (value "10k")
      (footprint "eagle-import:0603")
      (libsource (lib "eagle-import") (part "10KOHM-0603-1/10W-1%"))
    )
    (comp (ref "R58")
      (value "10k")
      (footprint "eagle-import:0603")
      (libsource (lib "eagle-import") (part "10KOHM-0603-1/10W-1%"))
    )
    (comp (ref "R59")
      (value "10k")
      (footprint "eagle-import:0603")
      (libsource (lib "eagle-import") (part "10KOHM-0603-1/10W-1%"))
    )
    (comp (ref "R60")
      (value "10k")
      (footprint "eagle-import:0603")
      (libsource (lib "eagle-import") (part "10KOHM-0603-1/10W-1%"))
    )
    (comp (ref "R61")
      (value "10k")
      (footprint "eagle-import:0603")
      (libsource (lib "eagle-import") (part "10KOHM-0603-1/10W-1%"))
    )
    (comp (ref "R62")
      (value "10k")
      (footprint "eagle-import:0603")
      (libsource (lib "eagle-import") (part "10KOHM-0603-1/10W-1%"))
    )
    (comp (ref "R63")
      (value "10k")
      (footprint "eagle-import:0603")
      (libsource (lib "eagle-import") (part "10KOHM-0603-1/10W-1%"))
    )
    (comp (ref "R64")
      (value "10k")
      (footprint "eagle-import:0603")
      (libsource (lib "eagle-import") (part "10KOHM-0603-1/10W-1%"))
    )
    (comp (ref "R65")
      (value "10k")
      (footprint "eagle-import:0603")
      (libsource (lib "eagle-import") (part "10KOHM-0603-1/10W-1%"))
    )
    (comp (ref "R66")
      (value "10k")
      (footprint "eagle-import:0603")
      (libsource (lib "eagle-import") (part "10KOHM-0603-1/10W-1%"))
    )
    (comp (ref "R67")
      (value "10k")
      (footprint "eagle-import:0603")
      (libsource (lib "eagle-import") (part "10KOHM-0603-1/10W-1%"))
    )
    (comp (ref "R68")
      (value "10k")
      (footprint "eagle-import:0603")
      (libsource (lib "eagle-import") (part "10KOHM-0603-1/10W-1%"))
    )
    (comp (ref "R69")
      (value "1k")
      (footprint "eagle-import:0603")
      (libsource (lib "eagle-import") (part "1KOHM-0603-1/10W-1%"))
    )
    (comp (ref "S1")
      (value "US2")
      (footprint "eagle-import:TACTILE_SWITCH_SMD_5.2MM")
      (libsource (lib "eagle-import") (part "MOMENTARY-SWITCH-SPST-SMD-5.2-REDUNDANT"))
    )
    (comp (ref "S2")
      (value "US2")
      (footprint "eagle-import:TACTILE_SWITCH_SMD_5.2MM")
      (libsource (lib "eagle-import") (part "MOMENTARY-SWITCH-SPST-SMD-5.2-REDUNDANT"))
    )
    (comp (ref "S3")
      (value "US2")
      (footprint "eagle-import:TACTILE_SWITCH_SMD_5.2MM")
      (libsource (lib "eagle-import") (part "MOMENTARY-SWITCH-SPST-SMD-5.2-REDUNDANT"))
    )
    (comp (ref "S4")
      (value "STM_!RST")
      (footprint "eagle-import:TACTILE_SWITCH_SMD_5.2MM")
      (libsource (lib "eagle-import") (part "MOMENTARY-SWITCH-SPST-SMD-5.2-REDUNDANT"))
    )
    (comp (ref "S5")
      (value "US1")
      (footprint "eagle-import:TACTILE_SWITCH_SMD_5.2MM")
      (libsource (lib "eagle-import") (part "MOMENTARY-SWITCH-SPST-SMD-5.2-REDUNDANT"))
    )
    (comp (ref "TP1")
      (value "EDRDY")
      (footprint "eagle-import:PAD.03X.04")
      (libsource (lib "eagle-import") (part "TEST-POINT3X4"))
    )
    (comp (ref "TP3")
      (value "ERX0")
      (footprint "eagle-import:PAD.03X.04")
      (libsource (lib "eagle-import") (part "TEST-POINT3X4"))
    )
    (comp (ref "TP4")
      (value "ETX0")
      (footprint "eagle-import:PAD.03X.04")
      (libsource (lib "eagle-import") (part "TEST-POINT3X4"))
    )
    (comp (ref "TP5")
      (value "E!RTS")
      (footprint "eagle-import:PAD.03X.04")
      (libsource (lib "eagle-import") (part "TEST-POINT3X4"))
    )
    (comp (ref "TP6")
      (value "E!DTR")
      (footprint "eagle-import:PAD.03X.04")
      (libsource (lib "eagle-import") (part "TEST-POINT3X4"))
    )
    (comp (ref "TP7")
      (value "EMOSI")
      (footprint "eagle-import:PAD.03X.04")
      (libsource (lib "eagle-import") (part "TEST-POINT3X4"))
    )
    (comp (ref "TP8")
      (value "EMISO")
      (footprint "eagle-import:PAD.03X.04")
      (libsource (lib "eagle-import") (part "TEST-POINT3X4"))
    )
    (comp (ref "TP9")
      (value "ESCLK")
      (footprint "eagle-import:PAD.03X.04")
      (libsource (lib "eagle-import") (part "TEST-POINT3X4"))
    )
    (comp (ref "TP10")
      (value "ECS")
      (footprint "eagle-import:PAD.03X.04")
      (libsource (lib "eagle-import") (part "TEST-POINT3X4"))
    )
    (comp (ref "TP11")
      (value "ESSI")
      (footprint "eagle-import:PAD.03X.04")
      (libsource (lib "eagle-import") (part "TEST-POINT3X4"))
    )
    (comp (ref "TP12")
      (value "ESSCK")
      (footprint "eagle-import:PAD.03X.04")
      (libsource (lib "eagle-import") (part "TEST-POINT3X4"))
    )
    (comp (ref "TP13")
      (value "E!RST")
      (footprint "eagle-import:PAD.03X.04")
      (libsource (lib "eagle-import") (part "TEST-POINT3X4"))
    )
    (comp (ref "TP17")
      (value "VDDIO")
      (footprint "eagle-import:PAD.03X.04")
      (libsource (lib "eagle-import") (part "TEST-POINT3X4"))
    )
    (comp (ref "TP18")
      (value "1V8")
      (footprint "eagle-import:PAD.03X.04")
      (libsource (lib "eagle-import") (part "TEST-POINT3X4"))
    )
    (comp (ref "TP20")
      (value "S1Si")
      (footprint "eagle-import:PAD.03X.04")
      (libsource (lib "eagle-import") (part "TEST-POINT3X4"))
    )
    (comp (ref "TP21")
      (value "S1SO")
      (footprint "eagle-import:PAD.03X.04")
      (libsource (lib "eagle-import") (part "TEST-POINT3X4"))
    )
    (comp (ref "TP22")
      (value "S1SCLk")
      (footprint "eagle-import:PAD.03X.04")
      (libsource (lib "eagle-import") (part "TEST-POINT3X4"))
    )
    (comp (ref "TP23")
      (value "CSSD")
      (footprint "eagle-import:PAD.03X.04")
      (libsource (lib "eagle-import") (part "TEST-POINT3X4"))
    )
    (comp (ref "TP24")
      (value "CSIMU")
      (footprint "eagle-import:PAD.03X.04")
      (libsource (lib "eagle-import") (part "TEST-POINT3X4"))
    )
    (comp (ref "TP25")
      (value "SDCD")
      (footprint "eagle-import:PAD.03X.04")
      (libsource (lib "eagle-import") (part "TEST-POINT3X4"))
    )
    (comp (ref "TP29")
      (value "CSIMUIO")
      (footprint "eagle-import:PAD.03X.04")
      (libsource (lib "eagle-import") (part "TEST-POINT3X4"))
    )
    (comp (ref "TP30")
      (value "IMUINT")
      (footprint "eagle-import:PAD.03X.04")
      (libsource (lib "eagle-import") (part "TEST-POINT3X4"))
    )
    (comp (ref "TP31")
      (value "IMUFS")
      (footprint "eagle-import:PAD.03X.04")
      (libsource (lib "eagle-import") (part "TEST-POINT3X4"))
    )
    (comp (ref "TP34")
      (value "AL1D")
      (footprint "eagle-import:PAD.03X.04")
      (libsource (lib "eagle-import") (part "TEST-POINT3X4"))
    )
    (comp (ref "TP35")
      (value "AL2D")
      (footprint "eagle-import:PAD.03X.04")
      (libsource (lib "eagle-import") (part "TEST-POINT3X4"))
    )
    (comp (ref "TP36")
      (value "AL3D")
      (footprint "eagle-import:PAD.03X.04")
      (libsource (lib "eagle-import") (part "TEST-POINT3X4"))
    )
    (comp (ref "TP37")
      (value "AL4D")
      (footprint "eagle-import:PAD.03X.04")
      (libsource (lib "eagle-import") (part "TEST-POINT3X4"))
    )
    (comp (ref "TP38")
      (value "AL1V")
      (footprint "eagle-import:PAD.03X.04")
      (libsource (lib "eagle-import") (part "TEST-POINT3X4"))
    )
    (comp (ref "TP39")
      (value "AL2V")
      (footprint "eagle-import:PAD.03X.04")
      (libsource (lib "eagle-import") (part "TEST-POINT3X4"))
    )
    (comp (ref "TP40")
      (value "AL3V")
      (footprint "eagle-import:PAD.03X.04")
      (libsource (lib "eagle-import") (part "TEST-POINT3X4"))
    )
    (comp (ref "TP41")
      (value "AL4V")
      (footprint "eagle-import:PAD.03X.04")
      (libsource (lib "eagle-import") (part "TEST-POINT3X4"))
    )
    (comp (ref "TP42")
      (value "AL1C")
      (footprint "eagle-import:PAD.03X.04")
      (libsource (lib "eagle-import") (part "TEST-POINT3X4"))
    )
    (comp (ref "TP43")
      (value "AL2C")
      (footprint "eagle-import:PAD.03X.04")
      (libsource (lib "eagle-import") (part "TEST-POINT3X4"))
    )
    (comp (ref "TP44")
      (value "AL3C")
      (footprint "eagle-import:PAD.03X.04")
      (libsource (lib "eagle-import") (part "TEST-POINT3X4"))
    )
    (comp (ref "TP45")
      (value "AL4C")
      (footprint "eagle-import:PAD.03X.04")
      (libsource (lib "eagle-import") (part "TEST-POINT3X4"))
    )
    (comp (ref "TP47")
      (value "VRPP")
      (footprint "eagle-import:PAD.03X.04")
      (libsource (lib "eagle-import") (part "TEST-POINT3X4"))
    )
    (comp (ref "TP48")
      (value "VOVP")
      (footprint "eagle-import:PAD.03X.04")
      (libsource (lib "eagle-import") (part "TEST-POINT3X4"))
    )
    (comp (ref "TP49")
      (value "VUSB")
      (footprint "eagle-import:PAD.03X.04")
      (libsource (lib "eagle-import") (part "TEST-POINT3X4"))
    )
    (comp (ref "TP50")
      (value "5V")
      (footprint "eagle-import:PAD.03X.04")
      (libsource (lib "eagle-import") (part "TEST-POINT3X4"))
    )
    (comp (ref "TP51")
      (value "3V3")
      (footprint "eagle-import:PAD.03X.04")
      (libsource (lib "eagle-import") (part "TEST-POINT3X4"))
    )
    (comp (ref "TP52")
      (value "GND")
      (footprint "eagle-import:PAD.03X.04")
      (libsource (lib "eagle-import") (part "TEST-POINT3X4"))
    )
    (comp (ref "TP53")
      (value "IIC1SDA")
      (footprint "eagle-import:PAD.03X.04")
      (libsource (lib "eagle-import") (part "TEST-POINT3X4"))
    )
    (comp (ref "TP54")
      (value "IIC1SCL")
      (footprint "eagle-import:PAD.03X.04")
      (libsource (lib "eagle-import") (part "TEST-POINT3X4"))
    )
    (comp (ref "TP57")
      (value "U7TX")
      (footprint "eagle-import:PAD.03X.04")
      (libsource (lib "eagle-import") (part "TEST-POINT3X4"))
    )
    (comp (ref "TP58")
      (value "U7RX")
      (footprint "eagle-import:PAD.03X.04")
      (libsource (lib "eagle-import") (part "TEST-POINT3X4"))
    )
    (comp (ref "TP62")
      (value "STMR")
      (footprint "eagle-import:PAD.03X.04")
      (libsource (lib "eagle-import") (part "TEST-POINT3X4"))
    )
    (comp (ref "TP68")
      (value "SWCLK")
      (footprint "eagle-import:PAD.03X.04")
      (libsource (lib "eagle-import") (part "TEST-POINT3X4"))
    )
    (comp (ref "TP69")
      (value "BRK")
      (footprint "eagle-import:PAD.03X.04")
      (libsource (lib "eagle-import") (part "TEST-POINT3X4"))
    )
    (comp (ref "TP70")
      (value "LTS")
      (footprint "eagle-import:PAD.03X.04")
      (libsource (lib "eagle-import") (part "TEST-POINT3X4"))
    )
    (comp (ref "TP71")
      (value "RTS")
      (footprint "eagle-import:PAD.03X.04")
      (libsource (lib "eagle-import") (part "TEST-POINT3X4"))
    )
    (comp (ref "TP72")
      (value "REV")
      (footprint "eagle-import:PAD.03X.04")
      (libsource (lib "eagle-import") (part "TEST-POINT3X4"))
    )
    (comp (ref "TP78")
      (value "SWDIO")
      (footprint "eagle-import:PAD.03X.04")
      (libsource (lib "eagle-import") (part "TEST-POINT3X4"))
    )
    (comp (ref "U$98")
      (value "REV_NUM")
      (footprint "eagle-import:REV_NUM")
      (fields (field (name "DESIGNER") "Owen Lyke") (field (name "REV") "v2.0.1"))
      (libsource (lib "eagle-import") (part "REV_NUM"))
    )
    (comp (ref "U1")
      (value "ESP-WROOM-32")
      (footprint "eagle-import:ESP-WROOM-32")
      (libsource (lib "eagle-import") (part "ESP-WROOM-32"))
    )
    (comp (ref "U3")
      (value "STM32F765VTG6")
      (footprint "eagle-import:LQFP-100")
      (libsource (lib "eagle-import") (part "STM32F765VTG6"))
    )
    (comp (ref "U4")
      (value "1.8V")
      (footprint "eagle-import:DDC5")
      (fields (field (name "MANUFACTURER_PART_NUMBER") "TPS78218DDCR"))
      (libsource (lib "eagle-import") (part "VREG_1.8_TPS78218DDCR"))
    )
    (comp (ref "U5")
      (value "9DoF IMU")
      (footprint "eagle-import:QFN24-3X3")
      (libsource (lib "eagle-import") (part "IMU_MPU9250-ICM20948"))
    )
    (comp (ref "U6")
      (value "TXB0108DQSR")
      (footprint "eagle-import:UFDFN-20")
      (libsource (lib "eagle-import") (part "TXB0108"))
    )
    (comp (ref "U7")
      (value "3.3V")
      (footprint "eagle-import:SOT23-5")
      (libsource (lib "eagle-import") (part "V_REG_AP2112K-3.3V"))
    )
    (comp (ref "U8")
      (value "CH340C")
      (footprint "eagle-import:SO016")
      (libsource (lib "eagle-import") (part "CH340C"))
    )
    (comp (ref "U9")
      (value "W25Q32FVSS")
      (footprint "eagle-import:SOIC-8")
      (libsource (lib "eagle-import") (part "W25Q32FVSS"))
    )
    (comp (ref "Y1")
      (value "24MHz")
      (footprint "eagle-import:CRYSTAL-SMD-5X3.2-4PAD")
      (libsource (lib "eagle-import") (part "CRYSTAL-24MHZ{dblquote}"))
    )
  )
  (nets
    (net (code "1") (name "/ESP_~{DTR}") (class "Default")
      (node (ref "Q1") (pin "6") (pinfunction "C_6") (pintype "passive"))
      (node (ref "R3") (pin "2") (pinfunction "2_2") (pintype "passive"))
      (node (ref "TP6") (pin "P$1") (pinfunction "1_P$1") (pintype "bidirectional"))
      (node (ref "U8") (pin "13") (pinfunction "~{DTR}_13") (pintype "bidirectional"))
    )
    (net (code "2") (name "/ESP_~{RESET}") (class "Default")
      (node (ref "C1") (pin "1") (pinfunction "1_1") (pintype "passive"))
      (node (ref "Q1") (pin "3") (pinfunction "C_3") (pintype "passive"))
      (node (ref "R9") (pin "1") (pinfunction "1_1") (pintype "passive"))
      (node (ref "S2") (pin "1") (pinfunction "1_1") (pintype "passive"))
      (node (ref "S2") (pin "2") (pinfunction "1_2") (pintype "passive"))
      (node (ref "TP13") (pin "P$1") (pinfunction "1_P$1") (pintype "bidirectional"))
      (node (ref "U1") (pin "3") (pinfunction "EN_3") (pintype "bidirectional"))
    )
    (net (code "3") (name "/ESP_~{RTS}") (class "Default")
      (node (ref "Q1") (pin "4") (pinfunction "E_4") (pintype "passive"))
      (node (ref "R4") (pin "2") (pinfunction "2_2") (pintype "passive"))
      (node (ref "TP5") (pin "P$1") (pinfunction "1_P$1") (pintype "bidirectional"))
      (node (ref "U8") (pin "14") (pinfunction "~{RTS}_14") (pintype "bidirectional"))
    )
    (net (code "4") (name "/STM_~{RESET}") (class "Default")
      (node (ref "C12") (pin "2") (pinfunction "2_2") (pintype "passive"))
      (node (ref "J3") (pin "10") (pinfunction "~{RESET}_10") (pintype "bidirectional"))
      (node (ref "R19") (pin "1") (pinfunction "1_1") (pintype "passive"))
      (node (ref "S4") (pin "1") (pinfunction "1_1") (pintype "passive"))
      (node (ref "S4") (pin "2") (pinfunction "1_2") (pintype "passive"))
      (node (ref "TP62") (pin "P$1") (pinfunction "1_P$1") (pintype "bidirectional"))
      (node (ref "U3") (pin "P$14") (pinfunction "14.NRST_P$14") (pintype "bidirectional"))
    )
    (net (code "5") (name "1.8V") (class "Default")
      (node (ref "JP9") (pin "3") (pinfunction "3_3") (pintype "passive"))
      (node (ref "TP18") (pin "P$1") (pinfunction "1_P$1") (pintype "bidirectional"))
      (node (ref "U4") (pin "5") (pinfunction "VOUT_5") (pintype "output"))
    )
    (net (code "6") (name "3.3V") (class "Default")
      (node (ref "C14") (pin "1") (pinfunction "1_1") (pintype "passive"))
      (node (ref "C16") (pin "1") (pinfunction "1_1") (pintype "passive"))
      (node (ref "C18") (pin "1") (pinfunction "1_1") (pintype "passive"))
      (node (ref "C2") (pin "1") (pinfunction "1_1") (pintype "passive"))
      (node (ref "C20") (pin "1") (pinfunction "1_1") (pintype "passive"))
      (node (ref "C3") (pin "1") (pinfunction "1_1") (pintype "passive"))
      (node (ref "C4") (pin "1") (pinfunction "1_1") (pintype "passive"))
      (node (ref "C5") (pin "1") (pinfunction "1_1") (pintype "passive"))
      (node (ref "C6") (pin "1") (pinfunction "1_1") (pintype "passive"))
      (node (ref "C9") (pin "1") (pinfunction "1_1") (pintype "passive"))
      (node (ref "D1") (pin "A") (pinfunction "A_A") (pintype "passive"))
      (node (ref "D12") (pin "A") (pinfunction "A_A") (pintype "passive"))
      (node (ref "D2") (pin "4VCC") (pinfunction "P$4_4VCC") (pintype "bidirectional"))
      (node (ref "D3") (pin "A") (pinfunction "A_A") (pintype "passive"))
      (node (ref "D4") (pin "A") (pinfunction "A_A") (pintype "passive"))
      (node (ref "D5") (pin "A") (pinfunction "A_A") (pintype "passive"))
      (node (ref "D6") (pin "A") (pinfunction "A_A") (pintype "passive"))
      (node (ref "D8") (pin "A") (pinfunction "A_A") (pintype "passive"))
      (node (ref "J3") (pin "1") (pinfunction "VCC_1") (pintype "bidirectional"))
      (node (ref "JP1") (pin "1") (pinfunction "1_1") (pintype "passive"))
      (node (ref "JP2") (pin "1") (pinfunction "1_1") (pintype "passive"))
      (node (ref "JP3") (pin "1") (pinfunction "1_1") (pintype "passive"))
      (node (ref "JP4") (pin "1") (pinfunction "1_1") (pintype "passive"))
      (node (ref "JP5") (pin "3") (pinfunction "3_3") (pintype "passive"))
      (node (ref "JP6") (pin "1") (pinfunction "1_1") (pintype "passive"))
      (node (ref "JP7") (pin "3") (pinfunction "3_3") (pintype "passive"))
      (node (ref "JP9") (pin "1") (pinfunction "1_1") (pintype "passive"))
      (node (ref "M1") (pin "P$2") (pinfunction "2_P$2") (pintype "passive"))
      (node (ref "M2") (pin "P$2") (pinfunction "2_P$2") (pintype "bidirectional"))
      (node (ref "M21") (pin "CD_SW2") (pinfunction "CD_SW2_CD_SW2") (pintype "bidirectional"))
      (node (ref "M21") (pin "P$4") (pinfunction "VDD_P$4") (pintype "bidirectional"))
      (node (ref "Q10") (pin "1") (pinfunction "G_1") (pintype "bidirectional"))
      (node (ref "Q12") (pin "1") (pinfunction "G_1") (pintype "bidirectional"))
      (node (ref "Q14") (pin "1") (pinfunction "G_1") (pintype "bidirectional"))
      (node (ref "Q16") (pin "1") (pinfunction "G_1") (pintype "bidirectional"))
      (node (ref "Q18") (pin "1") (pinfunction "G_1") (pintype "bidirectional"))
      (node (ref "Q19") (pin "1") (pinfunction "G_1") (pintype "bidirectional"))
      (node (ref "Q2") (pin "1") (pinfunction "G_1") (pintype "bidirectional"))
      (node (ref "Q20") (pin "1") (pinfunction "G_1") (pintype "bidirectional"))
      (node (ref "Q21") (pin "1") (pinfunction "G_1") (pintype "bidirectional"))
      (node (ref "Q3") (pin "1") (pinfunction "G_1") (pintype "bidirectional"))
      (node (ref "Q4") (pin "1") (pinfunction "G_1") (pintype "bidirectional"))
      (node (ref "Q5") (pin "1") (pinfunction "G_1") (pintype "bidirectional"))
      (node (ref "Q6") (pin "1") (pinfunction "G_1") (pintype "bidirectional"))
      (node (ref "Q7") (pin "1") (pinfunction "G_1") (pintype "bidirectional"))
      (node (ref "Q8") (pin "1") (pinfunction "G_1") (pintype "bidirectional"))
      (node (ref "Q9") (pin "1") (pinfunction "G_1") (pintype "bidirectional"))
      (node (ref "R17") (pin "2") (pinfunction "2_2") (pintype "passive"))
      (node (ref "R18") (pin "2") (pinfunction "2_2") (pintype "passive"))
      (node (ref "R19") (pin "2") (pinfunction "2_2") (pintype "passive"))
      (node (ref "R21") (pin "2") (pinfunction "2_2") (pintype "passive"))
      (node (ref "R22") (pin "2") (pinfunction "2_2") (pintype "passive"))
      (node (ref "R23") (pin "2") (pinfunction "2_2") (pintype "passive"))
      (node (ref "R24") (pin "2") (pinfunction "2_2") (pintype "passive"))
      (node (ref "R29") (pin "2") (pinfunction "2_2") (pintype "passive"))
      (node (ref "R30") (pin "2") (pinfunction "2_2") (pintype "passive"))
      (node (ref "R31") (pin "2") (pinfunction "2_2") (pintype "passive"))
      (node (ref "R32") (pin "2") (pinfunction "2_2") (pintype "passive"))
      (node (ref "R37") (pin "2") (pinfunction "2_2") (pintype "passive"))
      (node (ref "R39") (pin "2") (pinfunction "2_2") (pintype "passive"))
      (node (ref "R45") (pin "2") (pinfunction "2_2") (pintype "passive"))
      (node (ref "R47") (pin "2") (pinfunction "2_2") (pintype "passive"))
      (node (ref "R57") (pin "2") (pinfunction "2_2") (pintype "passive"))
      (node (ref "R58") (pin "2") (pinfunction "2_2") (pintype "passive"))
      (node (ref "R59") (pin "2") (pinfunction "2_2") (pintype "passive"))
      (node (ref "R6") (pin "2") (pinfunction "2_2") (pintype "passive"))
      (node (ref "R60") (pin "2") (pinfunction "2_2") (pintype "passive"))
      (node (ref "R65") (pin "2") (pinfunction "2_2") (pintype "passive"))
      (node (ref "R67") (pin "2") (pinfunction "2_2") (pintype "passive"))
      (node (ref "R9") (pin "2") (pinfunction "2_2") (pintype "passive"))
      (node (ref "S3") (pin "3") (pinfunction "2_3") (pintype "passive"))
      (node (ref "S3") (pin "4") (pinfunction "2_4") (pintype "passive"))
      (node (ref "S5") (pin "3") (pinfunction "2_3") (pintype "passive"))
      (node (ref "S5") (pin "4") (pinfunction "2_4") (pintype "passive"))
      (node (ref "TP51") (pin "P$1") (pinfunction "1_P$1") (pintype "bidirectional"))
      (node (ref "U1") (pin "2") (pinfunction "3V3_2") (pintype "bidirectional"))
      (node (ref "U3") (pin "P$100") (pinfunction "100.VDD_P$100") (pintype "bidirectional"))
      (node (ref "U3") (pin "P$11") (pinfunction "11.VDD_P$11") (pintype "bidirectional"))
      (node (ref "U3") (pin "P$20") (pinfunction "20.VREF_P$20") (pintype "bidirectional"))
      (node (ref "U3") (pin "P$21") (pinfunction "21.VDDA_P$21") (pintype "bidirectional"))
      (node (ref "U3") (pin "P$27") (pinfunction "27.VDD_P$27") (pintype "bidirectional"))
      (node (ref "U3") (pin "P$50") (pinfunction "50.VDD_P$50") (pintype "bidirectional"))
      (node (ref "U3") (pin "P$6") (pinfunction "6.VBAT_P$6") (pintype "bidirectional"))
      (node (ref "U3") (pin "P$75") (pinfunction "75.VDD_P$75") (pintype "bidirectional"))
      (node (ref "U4") (pin "1") (pinfunction "VIN_1") (pintype "input"))
      (node (ref "U4") (pin "3") (pinfunction "EN_3") (pintype "input"))
      (node (ref "U5") (pin "13") (pinfunction "VDD_13") (pintype "bidirectional"))
      (node (ref "U6") (pin "16") (pinfunction "VCCB_16") (pintype "bidirectional"))
      (node (ref "U7") (pin "5") (pinfunction "OUT_5") (pintype "passive"))
      (node (ref "U8") (pin "16") (pinfunction "VCC_16") (pintype "bidirectional"))
      (node (ref "U8") (pin "4") (pinfunction "V3_4") (pintype "bidirectional"))
      (node (ref "U9") (pin "8") (pinfunction "VCC_8") (pintype "bidirectional"))
    )
    (net (code "7") (name "5V") (class "Default")
      (node (ref "C17") (pin "1") (pinfunction "1_1") (pintype "passive"))
      (node (ref "D11") (pin "C") (pinfunction "C_C") (pintype "passive"))
      (node (ref "JP1") (pin "3") (pinfunction "3_3") (pintype "passive"))
      (node (ref "JP2") (pin "3") (pinfunction "3_3") (pintype "passive"))
      (node (ref "JP3") (pin "3") (pinfunction "3_3") (pintype "passive"))
      (node (ref "JP4") (pin "3") (pinfunction "3_3") (pintype "passive"))
      (node (ref "JP5") (pin "1") (pinfunction "1_1") (pintype "passive"))
      (node (ref "JP7") (pin "1") (pinfunction "1_1") (pintype "passive"))
      (node (ref "Q23") (pin "2") (pinfunction "S_2") (pintype "bidirectional"))
      (node (ref "TP50") (pin "P$1") (pinfunction "1_P$1") (pintype "bidirectional"))
      (node (ref "U7") (pin "1") (pinfunction "IN_1") (pintype "input"))
      (node (ref "U7") (pin "3") (pinfunction "EN_3") (pintype "input"))
    )
    (net (code "8") (name "ALED1_MOSI_VOUT") (class "Default")
      (node (ref "M3") (pin "P$1") (pinfunction "1_P$1") (pintype "bidirectional"))
      (node (ref "M7") (pin "P$1") (pinfunction "1_P$1") (pintype "passive"))
      (node (ref "Q6") (pin "3") (pinfunction "D_3") (pintype "bidirectional"))
      (node (ref "R33") (pin "1") (pinfunction "1_1") (pintype "passive"))
    )
    (net (code "9") (name "ALED1_SCLK_VOUT") (class "Default")
      (node (ref "M3") (pin "P$3") (pinfunction "3_P$3") (pintype "bidirectional"))
      (node (ref "M7") (pin "P$3") (pinfunction "3_P$3") (pintype "passive"))
      (node (ref "Q2") (pin "3") (pinfunction "D_3") (pintype "bidirectional"))
      (node (ref "R25") (pin "1") (pinfunction "1_1") (pintype "passive"))
    )
    (net (code "10") (name "ALED1_VOUT") (class "Default")
      (node (ref "JP1") (pin "2") (pinfunction "2_2") (pintype "passive"))
      (node (ref "R25") (pin "2") (pinfunction "2_2") (pintype "passive"))
      (node (ref "R33") (pin "2") (pinfunction "2_2") (pintype "passive"))
      (node (ref "TP38") (pin "P$1") (pinfunction "1_P$1") (pintype "bidirectional"))
    )
    (net (code "11") (name "ALED2_MOSI_VOUT") (class "Default")
      (node (ref "M4") (pin "P$1") (pinfunction "1_P$1") (pintype "bidirectional"))
      (node (ref "M8") (pin "P$1") (pinfunction "1_P$1") (pintype "passive"))
      (node (ref "Q7") (pin "3") (pinfunction "D_3") (pintype "bidirectional"))
      (node (ref "R34") (pin "1") (pinfunction "1_1") (pintype "passive"))
    )
    (net (code "12") (name "ALED2_SCLK_VOUT") (class "Default")
      (node (ref "M4") (pin "P$3") (pinfunction "3_P$3") (pintype "bidirectional"))
      (node (ref "M8") (pin "P$3") (pinfunction "3_P$3") (pintype "passive"))
      (node (ref "Q3") (pin "3") (pinfunction "D_3") (pintype "bidirectional"))
      (node (ref "R26") (pin "1") (pinfunction "1_1") (pintype "passive"))
    )
    (net (code "13") (name "ALED2_VOUT") (class "Default")
      (node (ref "JP2") (pin "2") (pinfunction "2_2") (pintype "passive"))
      (node (ref "R26") (pin "2") (pinfunction "2_2") (pintype "passive"))
      (node (ref "R34") (pin "2") (pinfunction "2_2") (pintype "passive"))
      (node (ref "TP39") (pin "P$1") (pinfunction "1_P$1") (pintype "bidirectional"))
    )
    (net (code "14") (name "ALED3_MOSI_VOUT") (class "Default")
      (node (ref "M5") (pin "P$1") (pinfunction "1_P$1") (pintype "bidirectional"))
      (node (ref "M9") (pin "P$1") (pinfunction "1_P$1") (pintype "passive"))
      (node (ref "Q8") (pin "3") (pinfunction "D_3") (pintype "bidirectional"))
      (node (ref "R35") (pin "1") (pinfunction "1_1") (pintype "passive"))
    )
    (net (code "15") (name "ALED3_SCLK_VOUT") (class "Default")
      (node (ref "M5") (pin "P$3") (pinfunction "3_P$3") (pintype "bidirectional"))
      (node (ref "M9") (pin "P$3") (pinfunction "3_P$3") (pintype "passive"))
      (node (ref "Q4") (pin "3") (pinfunction "D_3") (pintype "bidirectional"))
      (node (ref "R27") (pin "1") (pinfunction "1_1") (pintype "passive"))
    )
    (net (code "16") (name "ALED3_VOUT") (class "Default")
      (node (ref "JP3") (pin "2") (pinfunction "2_2") (pintype "passive"))
      (node (ref "R27") (pin "2") (pinfunction "2_2") (pintype "passive"))
      (node (ref "R35") (pin "2") (pinfunction "2_2") (pintype "passive"))
      (node (ref "TP40") (pin "P$1") (pinfunction "1_P$1") (pintype "bidirectional"))
    )
    (net (code "17") (name "ALED4_MOSI_VOUT") (class "Default")
      (node (ref "M10") (pin "P$1") (pinfunction "1_P$1") (pintype "passive"))
      (node (ref "M6") (pin "P$1") (pinfunction "1_P$1") (pintype "bidirectional"))
      (node (ref "Q9") (pin "3") (pinfunction "D_3") (pintype "bidirectional"))
      (node (ref "R36") (pin "1") (pinfunction "1_1") (pintype "passive"))
    )
    (net (code "18") (name "ALED4_SCLK_VOUT") (class "Default")
      (node (ref "M10") (pin "P$3") (pinfunction "3_P$3") (pintype "passive"))
      (node (ref "M6") (pin "P$3") (pinfunction "3_P$3") (pintype "bidirectional"))
      (node (ref "Q5") (pin "3") (pinfunction "D_3") (pintype "bidirectional"))
      (node (ref "R28") (pin "1") (pinfunction "1_1") (pintype "passive"))
    )
    (net (code "19") (name "ALED4_VOUT") (class "Default")
      (node (ref "JP4") (pin "2") (pinfunction "2_2") (pintype "passive"))
      (node (ref "R28") (pin "2") (pinfunction "2_2") (pintype "passive"))
      (node (ref "R36") (pin "2") (pinfunction "2_2") (pintype "passive"))
      (node (ref "TP41") (pin "P$1") (pinfunction "1_P$1") (pintype "bidirectional"))
    )
    (net (code "20") (name "BOOT0") (class "Default")
      (node (ref "JP6") (pin "2") (pinfunction "2_2") (pintype "passive"))
      (node (ref "R38") (pin "2") (pinfunction "2_2") (pintype "passive"))
      (node (ref "U3") (pin "P$94") (pinfunction "94.BOOT0_P$94") (pintype "bidirectional"))
    )
    (net (code "21") (name "BRK") (class "Default")
      (node (ref "Q18") (pin "2") (pinfunction "S_2") (pintype "bidirectional"))
      (node (ref "R57") (pin "1") (pinfunction "1_1") (pintype "passive"))
      (node (ref "TP69") (pin "P$1") (pinfunction "1_P$1") (pintype "bidirectional"))
      (node (ref "U3") (pin "P$81") (pinfunction "81.PD0_P$81") (pintype "bidirectional"))
    )
    (net (code "22") (name "BRK_12V") (class "Default")
      (node (ref "M19") (pin "P$1") (pinfunction "1_P$1") (pintype "bidirectional"))
      (node (ref "M20") (pin "P$1") (pinfunction "1_P$1") (pintype "passive"))
      (node (ref "Q18") (pin "3") (pinfunction "D_3") (pintype "bidirectional"))
      (node (ref "R61") (pin "1") (pinfunction "1_1") (pintype "passive"))
    )
    (net (code "23") (name "CS_ESP") (class "Default")
      (node (ref "TP10") (pin "P$1") (pinfunction "1_P$1") (pintype "bidirectional"))
      (node (ref "U1") (pin "29") (pinfunction "CS0_V/IO5_29") (pintype "bidirectional"))
      (node (ref "U3") (pin "P$4") (pinfunction "4.PE5_P$4") (pintype "bidirectional"))
    )
    (net (code "24") (name "CS_IMU") (class "Default")
      (node (ref "R67") (pin "1") (pinfunction "1_1") (pintype "passive"))
      (node (ref "TP24") (pin "P$1") (pinfunction "1_P$1") (pintype "bidirectional"))
      (node (ref "U3") (pin "P$3") (pinfunction "3.PE4_P$3") (pintype "bidirectional"))
      (node (ref "U6") (pin "20") (pinfunction "B1_20") (pintype "bidirectional"))
    )
    (net (code "25") (name "CS_IMU_VDDIO") (class "Default")
      (node (ref "TP29") (pin "P$1") (pinfunction "1_P$1") (pintype "bidirectional"))
      (node (ref "U5") (pin "22") (pinfunction "~{CS}_22") (pintype "bidirectional"))
      (node (ref "U6") (pin "1") (pinfunction "A1_1") (pintype "bidirectional"))
    )
    (net (code "26") (name "CS_SD") (class "Default")
      (node (ref "M21") (pin "P$2") (pinfunction "CD/DAT3_P$2") (pintype "bidirectional"))
      (node (ref "R65") (pin "1") (pinfunction "1_1") (pintype "passive"))
      (node (ref "TP23") (pin "P$1") (pinfunction "1_P$1") (pintype "bidirectional"))
      (node (ref "U3") (pin "P$2") (pinfunction "2.PE3_P$2") (pintype "bidirectional"))
    )
    (net (code "27") (name "DGND") (class "Default")
      (node (ref "C1") (pin "2") (pinfunction "2_2") (pintype "passive"))
      (node (ref "C10") (pin "2") (pinfunction "2_2") (pintype "passive"))
      (node (ref "C11") (pin "2") (pinfunction "2_2") (pintype "passive"))
      (node (ref "C12") (pin "1") (pinfunction "1_1") (pintype "passive"))
      (node (ref "C13") (pin "2") (pinfunction "2_2") (pintype "passive"))
      (node (ref "C14") (pin "2") (pinfunction "2_2") (pintype "passive"))
      (node (ref "C15") (pin "2") (pinfunction "2_2") (pintype "passive"))
      (node (ref "C16") (pin "2") (pinfunction "2_2") (pintype "passive"))
      (node (ref "C17") (pin "2") (pinfunction "2_2") (pintype "passive"))
      (node (ref "C18") (pin "2") (pinfunction "2_2") (pintype "passive"))
      (node (ref "C2") (pin "2") (pinfunction "2_2") (pintype "passive"))
      (node (ref "C20") (pin "2") (pinfunction "2_2") (pintype "passive"))
      (node (ref "C3") (pin "2") (pinfunction "2_2") (pintype "passive"))
      (node (ref "C4") (pin "2") (pinfunction "2_2") (pintype "passive"))
      (node (ref "C5") (pin "2") (pinfunction "2_2") (pintype "passive"))
      (node (ref "C6") (pin "2") (pinfunction "2_2") (pintype "passive"))
      (node (ref "C7") (pin "1") (pinfunction "1_1") (pintype "passive"))
      (node (ref "C8") (pin "1") (pinfunction "1_1") (pintype "passive"))
      (node (ref "C9") (pin "2") (pinfunction "2_2") (pintype "passive"))
      (node (ref "D10") (pin "A") (pinfunction "A_A") (pintype "passive"))
      (node (ref "D2") (pin "3GND") (pinfunction "P$3_3GND") (pintype "bidirectional"))
      (node (ref "J1") (pin "GND") (pinfunction "GND_GND") (pintype "power_in"))
      (node (ref "J2") (pin "GND") (pinfunction "GND_GND") (pintype "power_in"))
      (node (ref "J3") (pin "3") (pinfunction "GND_3") (pintype "bidirectional"))
      (node (ref "J3") (pin "5") (pinfunction "GND_5") (pintype "bidirectional"))
      (node (ref "J3") (pin "9") (pinfunction "GNDDTCT_9") (pintype "bidirectional"))
      (node (ref "M10") (pin "P$2") (pinfunction "2_P$2") (pintype "passive"))
      (node (ref "M11") (pin "P$4") (pinfunction "4_P$4") (pintype "bidirectional"))
      (node (ref "M13") (pin "P$4") (pinfunction "4_P$4") (pintype "bidirectional"))
      (node (ref "M15") (pin "P$4") (pinfunction "4_P$4") (pintype "passive"))
      (node (ref "M17") (pin "P$4") (pinfunction "4_P$4") (pintype "passive"))
      (node (ref "M21") (pin "P$6") (pinfunction "VSS1_P$6") (pintype "bidirectional"))
      (node (ref "M22") (pin "P$1") (pinfunction "1_P$1") (pintype "passive"))
      (node (ref "M23") (pin "P$2") (pinfunction "1_P$2") (pintype "bidirectional"))
      (node (ref "M3") (pin "P$2") (pinfunction "2_P$2") (pintype "bidirectional"))
      (node (ref "M4") (pin "P$2") (pinfunction "2_P$2") (pintype "bidirectional"))
      (node (ref "M5") (pin "P$2") (pinfunction "2_P$2") (pintype "bidirectional"))
      (node (ref "M6") (pin "P$2") (pinfunction "2_P$2") (pintype "bidirectional"))
      (node (ref "M7") (pin "P$2") (pinfunction "2_P$2") (pintype "passive"))
      (node (ref "M8") (pin "P$2") (pinfunction "2_P$2") (pintype "passive"))
      (node (ref "M9") (pin "P$2") (pinfunction "2_P$2") (pintype "passive"))
      (node (ref "Q22") (pin "1") (pinfunction "G_1") (pintype "bidirectional"))
      (node (ref "R1") (pin "1") (pinfunction "1_1") (pintype "passive"))
      (node (ref "R10") (pin "1") (pinfunction "1_1") (pintype "passive"))
      (node (ref "R16") (pin "1") (pinfunction "1_1") (pintype "passive"))
      (node (ref "R20") (pin "1") (pinfunction "1_1") (pintype "passive"))
      (node (ref "R38") (pin "1") (pinfunction "1_1") (pintype "passive"))
      (node (ref "R61") (pin "2") (pinfunction "2_2") (pintype "passive"))
      (node (ref "R62") (pin "2") (pinfunction "2_2") (pintype "passive"))
      (node (ref "R63") (pin "2") (pinfunction "2_2") (pintype "passive"))
      (node (ref "R64") (pin "2") (pinfunction "2_2") (pintype "passive"))
      (node (ref "R66") (pin "1") (pinfunction "1_1") (pintype "passive"))
      (node (ref "R68") (pin "1") (pinfunction "1_1") (pintype "passive"))
      (node (ref "R69") (pin "1") (pinfunction "1_1") (pintype "passive"))
      (node (ref "S1") (pin "3") (pinfunction "2_3") (pintype "passive"))
      (node (ref "S1") (pin "4") (pinfunction "2_4") (pintype "passive"))
      (node (ref "S2") (pin "3") (pinfunction "2_3") (pintype "passive"))
      (node (ref "S2") (pin "4") (pinfunction "2_4") (pintype "passive"))
      (node (ref "S4") (pin "3") (pinfunction "2_3") (pintype "passive"))
      (node (ref "S4") (pin "4") (pinfunction "2_4") (pintype "passive"))
      (node (ref "TP52") (pin "P$1") (pinfunction "1_P$1") (pintype "bidirectional"))
      (node (ref "U1") (pin "1") (pinfunction "GND_1") (pintype "bidirectional"))
      (node (ref "U1") (pin "15") (pinfunction "GND_15") (pintype "bidirectional"))
      (node (ref "U1") (pin "38") (pinfunction "GND_38") (pintype "bidirectional"))
      (node (ref "U1") (pin "GND") (pinfunction "GND_GND") (pintype "bidirectional"))
      (node (ref "U3") (pin "P$10") (pinfunction "10.VSS_P$10") (pintype "bidirectional"))
      (node (ref "U3") (pin "P$19") (pinfunction "19.VSSA_P$19") (pintype "bidirectional"))
      (node (ref "U3") (pin "P$26") (pinfunction "26.VSS_P$26") (pintype "bidirectional"))
      (node (ref "U3") (pin "P$49") (pinfunction "49.VSS_P$49") (pintype "bidirectional"))
      (node (ref "U3") (pin "P$74") (pinfunction "74.VSS_P$74") (pintype "bidirectional"))
      (node (ref "U3") (pin "P$99") (pinfunction "99.VSS_P$99") (pintype "bidirectional"))
      (node (ref "U4") (pin "2") (pinfunction "GND_2") (pintype "power_in"))
      (node (ref "U4") (pin "4") (pinfunction "GND_4") (pintype "power_in"))
      (node (ref "U5") (pin "18") (pinfunction "GND_18") (pintype "bidirectional"))
      (node (ref "U5") (pin "20") (pinfunction "RESV20_20") (pintype "bidirectional"))
      (node (ref "U6") (pin "15") (pinfunction "GND_15") (pintype "bidirectional"))
      (node (ref "U7") (pin "2") (pinfunction "GND_2") (pintype "input"))
      (node (ref "U8") (pin "1") (pinfunction "GND_1") (pintype "bidirectional"))
      (node (ref "U9") (pin "4") (pinfunction "GND_4") (pintype "bidirectional"))
      (node (ref "Y1") (pin "2") (pinfunction "GND_2") (pintype "bidirectional"))
      (node (ref "Y1") (pin "4") (pinfunction "GND_4") (pintype "bidirectional"))
    )
    (net (code "28") (name "ESP_0") (class "Default")
      (node (ref "Q1") (pin "1") (pinfunction "E_1") (pintype "passive"))
      (node (ref "R6") (pin "1") (pinfunction "1_1") (pintype "passive"))
      (node (ref "S1") (pin "1") (pinfunction "1_1") (pintype "passive"))
      (node (ref "S1") (pin "2") (pinfunction "1_2") (pintype "passive"))
      (node (ref "U1") (pin "25") (pinfunction "IO0_25") (pintype "bidirectional"))
    )
    (net (code "29") (name "ESP_DRDY") (class "Default")
      (node (ref "TP1") (pin "P$1") (pinfunction "1_P$1") (pintype "bidirectional"))
      (node (ref "U1") (pin "24") (pinfunction "IO2_24") (pintype "bidirectional"))
      (node (ref "U3") (pin "P$9") (pinfunction "9.PC15_P$9") (pintype "bidirectional"))
    )
    (net (code "30") (name "ESP_RXI0") (class "Default")
      (node (ref "R8") (pin "1") (pinfunction "1_1") (pintype "passive"))
      (node (ref "TP3") (pin "P$1") (pinfunction "1_P$1") (pintype "bidirectional"))
      (node (ref "U1") (pin "34") (pinfunction "RXD_34") (pintype "bidirectional"))
      (node (ref "U8") (pin "2") (pinfunction "TXO_2") (pintype "bidirectional"))
    )
    (net (code "31") (name "ESP_STAT_MOSI") (class "Default")
      (node (ref "D2") (pin "1DIN") (pinfunction "P$1_1DIN") (pintype "bidirectional"))
      (node (ref "TP11") (pin "P$1") (pinfunction "1_P$1") (pintype "bidirectional"))
      (node (ref "U1") (pin "16") (pinfunction "MOSI_H/IO13_16") (pintype "bidirectional"))
    )
    (net (code "32") (name "ESP_STAT_SCLK") (class "Default")
      (node (ref "D2") (pin "2CIN") (pinfunction "P$2_2CIN") (pintype "bidirectional"))
      (node (ref "TP12") (pin "P$1") (pinfunction "1_P$1") (pintype "bidirectional"))
      (node (ref "U1") (pin "13") (pinfunction "SCK_H/IO14_13") (pintype "bidirectional"))
    )
    (net (code "33") (name "ESP_TXO0") (class "Default")
      (node (ref "R7") (pin "1") (pinfunction "1_1") (pintype "passive"))
      (node (ref "TP4") (pin "P$1") (pinfunction "1_P$1") (pintype "bidirectional"))
      (node (ref "U1") (pin "35") (pinfunction "TXD_35") (pintype "bidirectional"))
      (node (ref "U8") (pin "3") (pinfunction "RXI_3") (pintype "bidirectional"))
    )
    (net (code "34") (name "ESP_USB_DM") (class "Default")
      (node (ref "J1") (pin "D-") (pinfunction "D-_D-") (pintype "bidirectional"))
      (node (ref "U8") (pin "6") (pinfunction "UD-_6") (pintype "bidirectional"))
    )
    (net (code "35") (name "ESP_USB_DP") (class "Default")
      (node (ref "J1") (pin "D+") (pinfunction "D+_D+") (pintype "bidirectional"))
      (node (ref "U8") (pin "5") (pinfunction "UD+_5") (pintype "bidirectional"))
    )
    (net (code "36") (name "I2C1_SCL") (class "Default")
      (node (ref "Q10") (pin "2") (pinfunction "S_2") (pintype "bidirectional"))
      (node (ref "R37") (pin "1") (pinfunction "1_1") (pintype "passive"))
      (node (ref "TP54") (pin "P$1") (pinfunction "1_P$1") (pintype "bidirectional"))
      (node (ref "U3") (pin "P$95") (pinfunction "95.PB8_P$95") (pintype "bidirectional"))
    )
    (net (code "37") (name "I2C1_SCL_VOUT") (class "Default")
      (node (ref "M11") (pin "P$1") (pinfunction "1_P$1") (pintype "bidirectional"))
      (node (ref "M15") (pin "P$1") (pinfunction "1_P$1") (pintype "passive"))
      (node (ref "Q10") (pin "3") (pinfunction "D_3") (pintype "bidirectional"))
      (node (ref "R41") (pin "1") (pinfunction "1_1") (pintype "passive"))
    )
    (net (code "38") (name "I2C1_SDA") (class "Default")
      (node (ref "Q14") (pin "2") (pinfunction "S_2") (pintype "bidirectional"))
      (node (ref "R45") (pin "1") (pinfunction "1_1") (pintype "passive"))
      (node (ref "TP53") (pin "P$1") (pinfunction "1_P$1") (pintype "bidirectional"))
      (node (ref "U3") (pin "P$93") (pinfunction "93.PB7_P$93") (pintype "bidirectional"))
    )
    (net (code "39") (name "I2C1_SDA_VOUT") (class "Default")
      (node (ref "M11") (pin "P$2") (pinfunction "2_P$2") (pintype "bidirectional"))
      (node (ref "M15") (pin "P$2") (pinfunction "2_P$2") (pintype "passive"))
      (node (ref "Q14") (pin "3") (pinfunction "D_3") (pintype "bidirectional"))
      (node (ref "R49") (pin "1") (pinfunction "1_1") (pintype "passive"))
    )
    (net (code "40") (name "I2C1_VOUT") (class "Default")
      (node (ref "JP5") (pin "2") (pinfunction "2_2") (pintype "passive"))
      (node (ref "M11") (pin "P$3") (pinfunction "3_P$3") (pintype "bidirectional"))
      (node (ref "M15") (pin "P$3") (pinfunction "3_P$3") (pintype "passive"))
      (node (ref "R41") (pin "2") (pinfunction "2_2") (pintype "passive"))
      (node (ref "R49") (pin "2") (pinfunction "2_2") (pintype "passive"))
    )
    (net (code "41") (name "I2C2_SCL") (class "Default")
      (node (ref "U3") (pin "P$46") (pinfunction "46.PB10_P$46") (pintype "bidirectional"))
    )
    (net (code "42") (name "I2C2_SDA") (class "Default")
      (node (ref "U3") (pin "P$47") (pinfunction "47.PB11_P$47") (pintype "bidirectional"))
    )
    (net (code "43") (name "IMU_FSYNC") (class "Default")
      (node (ref "TP31") (pin "P$1") (pinfunction "1_P$1") (pintype "bidirectional"))
      (node (ref "U3") (pin "P$64") (pinfunction "64.PC7_P$64") (pintype "bidirectional"))
      (node (ref "U6") (pin "12") (pinfunction "B7_12") (pintype "bidirectional"))
    )
    (net (code "44") (name "IMU_FSYNC_VDDIO") (class "Default")
      (node (ref "U5") (pin "11") (pinfunction "FSYNC_11") (pintype "bidirectional"))
      (node (ref "U6") (pin "9") (pinfunction "A7_9") (pintype "bidirectional"))
    )
    (net (code "45") (name "IMU_INT") (class "Default")
      (node (ref "TP30") (pin "P$1") (pinfunction "1_P$1") (pintype "bidirectional"))
      (node (ref "U3") (pin "P$63") (pinfunction "63.PC6_P$63") (pintype "bidirectional"))
      (node (ref "U6") (pin "11") (pinfunction "B8_11") (pintype "bidirectional"))
    )
    (net (code "46") (name "IMU_INT_VDDIO") (class "Default")
      (node (ref "U5") (pin "12") (pinfunction "INT_12") (pintype "bidirectional"))
      (node (ref "U6") (pin "10") (pinfunction "A8_10") (pintype "bidirectional"))
    )
    (net (code "47") (name "IMU_RESV1") (class "Default")
      (node (ref "JP10") (pin "1") (pinfunction "1_1") (pintype "passive"))
      (node (ref "U5") (pin "1") (pinfunction "RESV1_1") (pintype "bidirectional"))
    )
    (net (code "48") (name "IMU_VDDIO") (class "Default")
      (node (ref "C13") (pin "1") (pinfunction "1_1") (pintype "passive"))
      (node (ref "JP10") (pin "2") (pinfunction "2_2") (pintype "passive"))
      (node (ref "JP9") (pin "2") (pinfunction "2_2") (pintype "passive"))
      (node (ref "TP17") (pin "P$1") (pinfunction "1_P$1") (pintype "bidirectional"))
      (node (ref "U5") (pin "8") (pinfunction "VDDIO_8") (pintype "bidirectional"))
      (node (ref "U6") (pin "5") (pinfunction "VCCA_5") (pintype "bidirectional"))
      (node (ref "U6") (pin "6") (pinfunction "OE_6") (pintype "bidirectional"))
    )
    (net (code "49") (name "LTS") (class "Default")
      (node (ref "Q19") (pin "2") (pinfunction "S_2") (pintype "bidirectional"))
      (node (ref "R58") (pin "1") (pinfunction "1_1") (pintype "passive"))
      (node (ref "TP70") (pin "P$1") (pinfunction "1_P$1") (pintype "bidirectional"))
      (node (ref "U3") (pin "P$82") (pinfunction "82.PD1_P$82") (pintype "bidirectional"))
    )
    (net (code "50") (name "LTS_12V") (class "Default")
      (node (ref "M19") (pin "P$2") (pinfunction "2_P$2") (pintype "bidirectional"))
      (node (ref "M20") (pin "P$2") (pinfunction "2_P$2") (pintype "passive"))
      (node (ref "Q19") (pin "3") (pinfunction "D_3") (pintype "bidirectional"))
      (node (ref "R62") (pin "1") (pinfunction "1_1") (pintype "passive"))
    )
    (net (code "51") (name "Net-(D1-PadC)") (class "Default")
      (node (ref "D1") (pin "C") (pinfunction "C_C") (pintype "passive"))
      (node (ref "R7") (pin "2") (pinfunction "2_2") (pintype "passive"))
    )
    (net (code "52") (name "Net-(D3-PadC)") (class "Default")
      (node (ref "D3") (pin "C") (pinfunction "C_C") (pintype "passive"))
      (node (ref "R8") (pin "2") (pinfunction "2_2") (pintype "passive"))
    )
    (net (code "53") (name "Net-(D4-PadC)") (class "Default")
      (node (ref "D4") (pin "C") (pinfunction "C_C") (pintype "passive"))
      (node (ref "R11") (pin "2") (pinfunction "2_2") (pintype "passive"))
    )
    (net (code "54") (name "Net-(D5-PadC)") (class "Default")
      (node (ref "D5") (pin "C") (pinfunction "C_C") (pintype "passive"))
      (node (ref "R12") (pin "2") (pinfunction "2_2") (pintype "passive"))
    )
    (net (code "55") (name "Net-(D6-PadC)") (class "Default")
      (node (ref "D6") (pin "C") (pinfunction "C_C") (pintype "passive"))
      (node (ref "R53") (pin "2") (pinfunction "2_2") (pintype "passive"))
    )
    (net (code "56") (name "Net-(D8-PadC)") (class "Default")
      (node (ref "D8") (pin "C") (pinfunction "C_C") (pintype "passive"))
      (node (ref "R55") (pin "2") (pinfunction "2_2") (pintype "passive"))
    )
    (net (code "57") (name "Net-(D12-PadC)") (class "Default")
      (node (ref "D12") (pin "C") (pinfunction "C_C") (pintype "passive"))
      (node (ref "R69") (pin "2") (pinfunction "2_2") (pintype "passive"))
    )
    (net (code "58") (name "Net-(J1-PadSHIELD)") (class "Default")
      (node (ref "J1") (pin "SHIELD") (pinfunction "SHIELD_SHIELD") (pintype "bidirectional"))
      (node (ref "J1") (pin "SHIELD10") (pinfunction "SHIELD_SHIELD10") (pintype "bidirectional"))
      (node (ref "J1") (pin "SHIELD2") (pinfunction "SHIELD_SHIELD2") (pintype "bidirectional"))
      (node (ref "J1") (pin "SHIELD3") (pinfunction "SHIELD_SHIELD3") (pintype "bidirectional"))
      (node (ref "J1") (pin "SHIELD4") (pinfunction "SHIELD_SHIELD4") (pintype "bidirectional"))
      (node (ref "J1") (pin "SHIELD5") (pinfunction "SHIELD_SHIELD5") (pintype "bidirectional"))
      (node (ref "J1") (pin "SHIELD6") (pinfunction "SHIELD_SHIELD6") (pintype "bidirectional"))
      (node (ref "J1") (pin "SHIELD7") (pinfunction "SHIELD_SHIELD7") (pintype "bidirectional"))
      (node (ref "J1") (pin "SHIELD8") (pinfunction "SHIELD_SHIELD8") (pintype "bidirectional"))
      (node (ref "J1") (pin "SHIELD9") (pinfunction "SHIELD_SHIELD9") (pintype "bidirectional"))
      (node (ref "R1") (pin "2") (pinfunction "2_2") (pintype "passive"))
    )
    (net (code "59") (name "Net-(J2-PadSHIELD)") (class "Default")
      (node (ref "J2") (pin "SHIELD") (pinfunction "SHIELD_SHIELD") (pintype "bidirectional"))
      (node (ref "J2") (pin "SHIELD10") (pinfunction "SHIELD_SHIELD10") (pintype "bidirectional"))
      (node (ref "J2") (pin "SHIELD2") (pinfunction "SHIELD_SHIELD2") (pintype "bidirectional"))
      (node (ref "J2") (pin "SHIELD3") (pinfunction "SHIELD_SHIELD3") (pintype "bidirectional"))
      (node (ref "J2") (pin "SHIELD4") (pinfunction "SHIELD_SHIELD4") (pintype "bidirectional"))
      (node (ref "J2") (pin "SHIELD5") (pinfunction "SHIELD_SHIELD5") (pintype "bidirectional"))
      (node (ref "J2") (pin "SHIELD6") (pinfunction "SHIELD_SHIELD6") (pintype "bidirectional"))
      (node (ref "J2") (pin "SHIELD7") (pinfunction "SHIELD_SHIELD7") (pintype "bidirectional"))
      (node (ref "J2") (pin "SHIELD8") (pinfunction "SHIELD_SHIELD8") (pintype "bidirectional"))
      (node (ref "J2") (pin "SHIELD9") (pinfunction "SHIELD_SHIELD9") (pintype "bidirectional"))
      (node (ref "R10") (pin "2") (pinfunction "2_2") (pintype "passive"))
    )
    (net (code "60") (name "Net-(J3-SWDCLK{slash}TCK)") (class "Default")
      (node (ref "J3") (pin "4") (pinfunction "SWDCLK/TCK_4") (pintype "bidirectional"))
      (node (ref "R14") (pin "1") (pinfunction "1_1") (pintype "passive"))
    )
    (net (code "61") (name "Net-(J3-SWDIO{slash}TMS)") (class "Default")
      (node (ref "J3") (pin "2") (pinfunction "SWDIO/TMS_2") (pintype "bidirectional"))
      (node (ref "R13") (pin "1") (pinfunction "1_1") (pintype "passive"))
    )
    (net (code "62") (name "Net-(Q1A-B)") (class "Default")
      (node (ref "Q1") (pin "5") (pinfunction "B_5") (pintype "passive"))
      (node (ref "R3") (pin "1") (pinfunction "1_1") (pintype "passive"))
    )
    (net (code "63") (name "Net-(Q1B-B)") (class "Default")
      (node (ref "Q1") (pin "2") (pinfunction "B_2") (pintype "passive"))
      (node (ref "R4") (pin "1") (pinfunction "1_1") (pintype "passive"))
    )
    (net (code "64") (name "Net-(U3-48.VCAP1)") (class "Default")
      (node (ref "C10") (pin "1") (pinfunction "1_1") (pintype "passive"))
      (node (ref "U3") (pin "P$48") (pinfunction "48.VCAP1_P$48") (pintype "bidirectional"))
    )
    (net (code "65") (name "Net-(U3-73.VCAP2)") (class "Default")
      (node (ref "C11") (pin "1") (pinfunction "1_1") (pintype "passive"))
      (node (ref "U3") (pin "P$73") (pinfunction "73.VCAP2_P$73") (pintype "bidirectional"))
    )
    (net (code "66") (name "Net-(U5-REGOUT)") (class "Default")
      (node (ref "C15") (pin "1") (pinfunction "1_1") (pintype "passive"))
      (node (ref "U5") (pin "10") (pinfunction "REGOUT_10") (pintype "bidirectional"))
    )
    (net (code "67") (name "PH0") (class "Default")
      (node (ref "C7") (pin "2") (pinfunction "2_2") (pintype "passive"))
      (node (ref "U3") (pin "P$12") (pinfunction "12.PH0_P$12") (pintype "bidirectional"))
      (node (ref "Y1") (pin "3") (pinfunction "2_3") (pintype "passive"))
    )
    (net (code "68") (name "PH1") (class "Default")
      (node (ref "C8") (pin "2") (pinfunction "2_2") (pintype "passive"))
      (node (ref "U3") (pin "P$13") (pinfunction "13.PH1_P$13") (pintype "bidirectional"))
      (node (ref "Y1") (pin "1") (pinfunction "1_1") (pintype "passive"))
    )
    (net (code "69") (name "QSPI_BK1_IO0") (class "Default")
      (node (ref "Q9") (pin "2") (pinfunction "S_2") (pintype "bidirectional"))
      (node (ref "R32") (pin "1") (pinfunction "1_1") (pintype "passive"))
      (node (ref "TP37") (pin "P$1") (pinfunction "1_P$1") (pintype "bidirectional"))
      (node (ref "U3") (pin "P$58") (pinfunction "58.PD11_P$58") (pintype "bidirectional"))
    )
    (net (code "70") (name "QSPI_BK1_IO1") (class "Default")
      (node (ref "U3") (pin "P$59") (pinfunction "59.PD12_P$59") (pintype "bidirectional"))
    )
    (net (code "71") (name "QSPI_BK1_IO2") (class "Default")
      (node (ref "U3") (pin "P$1") (pinfunction "1.PE2_P$1") (pintype "bidirectional"))
    )
    (net (code "72") (name "QSPI_BK1_IO3") (class "Default")
      (node (ref "U3") (pin "P$60") (pinfunction "60.PD13_P$60") (pintype "bidirectional"))
    )
    (net (code "73") (name "QSPI_BK1_NCS") (class "Default")
      (node (ref "U3") (pin "P$92") (pinfunction "92.PB6_P$92") (pintype "bidirectional"))
    )
    (net (code "74") (name "QSPI_BK2_IO0") (class "Default")
      (node (ref "U3") (pin "P$37") (pinfunction "37.PE7_P$37") (pintype "bidirectional"))
      (node (ref "U9") (pin "5") (pinfunction "SI(D0)_5") (pintype "bidirectional"))
    )
    (net (code "75") (name "QSPI_BK2_IO1") (class "Default")
      (node (ref "U3") (pin "P$38") (pinfunction "38.PE8_P$38") (pintype "bidirectional"))
      (node (ref "U9") (pin "2") (pinfunction "SO(D1)_2") (pintype "bidirectional"))
    )
    (net (code "76") (name "QSPI_BK2_IO2") (class "Default")
      (node (ref "U3") (pin "P$39") (pinfunction "39.PE9_P$39") (pintype "bidirectional"))
      (node (ref "U9") (pin "3") (pinfunction "~{WP}(D2)_3") (pintype "bidirectional"))
    )
    (net (code "77") (name "QSPI_BK2_IO3") (class "Default")
      (node (ref "U3") (pin "P$40") (pinfunction "40.PE10_P$40") (pintype "bidirectional"))
      (node (ref "U9") (pin "7") (pinfunction "~{HOLD}(D3)_7") (pintype "bidirectional"))
    )
    (net (code "78") (name "QSPI_BK2_NCS") (class "Default")
      (node (ref "U3") (pin "P$79") (pinfunction "79.PC11_P$79") (pintype "bidirectional"))
      (node (ref "U9") (pin "1") (pinfunction "~{CS}_1") (pintype "bidirectional"))
    )
    (net (code "79") (name "QSPI_SCLK") (class "Default")
      (node (ref "Q5") (pin "2") (pinfunction "S_2") (pintype "bidirectional"))
      (node (ref "R24") (pin "1") (pinfunction "1_1") (pintype "passive"))
      (node (ref "TP45") (pin "P$1") (pinfunction "1_P$1") (pintype "bidirectional"))
      (node (ref "U3") (pin "P$36") (pinfunction "36.PB2_P$36") (pintype "bidirectional"))
      (node (ref "U9") (pin "6") (pinfunction "SCK_6") (pintype "bidirectional"))
    )
    (net (code "80") (name "REV") (class "Default")
      (node (ref "Q21") (pin "2") (pinfunction "S_2") (pintype "bidirectional"))
      (node (ref "R60") (pin "1") (pinfunction "1_1") (pintype "passive"))
      (node (ref "TP72") (pin "P$1") (pinfunction "1_P$1") (pintype "bidirectional"))
      (node (ref "U3") (pin "P$84") (pinfunction "84.PD3_P$84") (pintype "bidirectional"))
    )
    (net (code "81") (name "REV_12V") (class "Default")
      (node (ref "M19") (pin "P$4") (pinfunction "4_P$4") (pintype "bidirectional"))
      (node (ref "M20") (pin "P$4") (pinfunction "4_P$4") (pintype "passive"))
      (node (ref "Q21") (pin "3") (pinfunction "D_3") (pintype "bidirectional"))
      (node (ref "R64") (pin "1") (pinfunction "1_1") (pintype "passive"))
    )
    (net (code "82") (name "RTS") (class "Default")
      (node (ref "Q20") (pin "2") (pinfunction "S_2") (pintype "bidirectional"))
      (node (ref "R59") (pin "1") (pinfunction "1_1") (pintype "passive"))
      (node (ref "TP71") (pin "P$1") (pinfunction "1_P$1") (pintype "bidirectional"))
      (node (ref "U3") (pin "P$83") (pinfunction "83.PD2_P$83") (pintype "bidirectional"))
    )
    (net (code "83") (name "RTS_12V") (class "Default")
      (node (ref "M19") (pin "P$3") (pinfunction "3_P$3") (pintype "bidirectional"))
      (node (ref "M20") (pin "P$3") (pinfunction "3_P$3") (pintype "passive"))
      (node (ref "Q20") (pin "3") (pinfunction "D_3") (pintype "bidirectional"))
      (node (ref "R63") (pin "1") (pinfunction "1_1") (pintype "passive"))
    )
    (net (code "84") (name "SD_CD") (class "Default")
      (node (ref "M21") (pin "CD_SW1") (pinfunction "CD_SW1_CD_SW1") (pintype "bidirectional"))
      (node (ref "R66") (pin "2") (pinfunction "2_2") (pintype "passive"))
      (node (ref "TP25") (pin "P$1") (pinfunction "1_P$1") (pintype "bidirectional"))
      (node (ref "U3") (pin "P$15") (pinfunction "15.PC0_P$15") (pintype "bidirectional"))
    )
    (net (code "85") (name "SPI1_MISO") (class "Default")
      (node (ref "M21") (pin "P$7") (pinfunction "DAT0_P$7") (pintype "bidirectional"))
      (node (ref "TP21") (pin "P$1") (pinfunction "1_P$1") (pintype "bidirectional"))
      (node (ref "U3") (pin "P$30") (pinfunction "30.PA6_P$30") (pintype "bidirectional"))
      (node (ref "U6") (pin "13") (pinfunction "B6_13") (pintype "bidirectional"))
    )
    (net (code "86") (name "SPI1_MISO_VDDIO") (class "Default")
      (node (ref "U5") (pin "9") (pinfunction "AD0/SDO_9") (pintype "bidirectional"))
      (node (ref "U6") (pin "8") (pinfunction "A6_8") (pintype "bidirectional"))
    )
    (net (code "87") (name "SPI1_MOSI") (class "Default")
      (node (ref "M21") (pin "P$3") (pinfunction "CMD_P$3") (pintype "bidirectional"))
      (node (ref "TP20") (pin "P$1") (pinfunction "1_P$1") (pintype "bidirectional"))
      (node (ref "U3") (pin "P$88") (pinfunction "88.PD7_P$88") (pintype "bidirectional"))
      (node (ref "U6") (pin "18") (pinfunction "B3_18") (pintype "bidirectional"))
    )
    (net (code "88") (name "SPI1_MOSI_VDDIO") (class "Default")
      (node (ref "U5") (pin "24") (pinfunction "SDA/SDI_24") (pintype "bidirectional"))
      (node (ref "U6") (pin "3") (pinfunction "A3_3") (pintype "bidirectional"))
    )
    (net (code "89") (name "SPI1_SCLK") (class "Default")
      (node (ref "M21") (pin "P$5") (pinfunction "CLK_P$5") (pintype "bidirectional"))
      (node (ref "TP22") (pin "P$1") (pinfunction "1_P$1") (pintype "bidirectional"))
      (node (ref "U3") (pin "P$89") (pinfunction "89.PB3_P$89") (pintype "bidirectional"))
      (node (ref "U6") (pin "19") (pinfunction "B2_19") (pintype "bidirectional"))
    )
    (net (code "90") (name "SPI1_SCLK_VDDIO") (class "Default")
      (node (ref "U5") (pin "23") (pinfunction "SCL/SCLK_23") (pintype "bidirectional"))
      (node (ref "U6") (pin "2") (pinfunction "A2_2") (pintype "bidirectional"))
    )
    (net (code "91") (name "SPI2_MOSI") (class "Default")
      (node (ref "Q6") (pin "2") (pinfunction "S_2") (pintype "bidirectional"))
      (node (ref "R29") (pin "1") (pinfunction "1_1") (pintype "passive"))
      (node (ref "TP34") (pin "P$1") (pinfunction "1_P$1") (pintype "bidirectional"))
      (node (ref "U3") (pin "P$16") (pinfunction "16.PC1_P$16") (pintype "bidirectional"))
    )
    (net (code "92") (name "SPI2_SCLK") (class "Default")
      (node (ref "Q2") (pin "2") (pinfunction "S_2") (pintype "bidirectional"))
      (node (ref "R21") (pin "1") (pinfunction "1_1") (pintype "passive"))
      (node (ref "TP42") (pin "P$1") (pinfunction "1_P$1") (pintype "bidirectional"))
      (node (ref "U3") (pin "P$52") (pinfunction "52.PB13_P$52") (pintype "bidirectional"))
    )
    (net (code "93") (name "SPI3_MOSI") (class "Default")
      (node (ref "Q7") (pin "2") (pinfunction "S_2") (pintype "bidirectional"))
      (node (ref "R30") (pin "1") (pinfunction "1_1") (pintype "passive"))
      (node (ref "TP35") (pin "P$1") (pinfunction "1_P$1") (pintype "bidirectional"))
      (node (ref "U3") (pin "P$87") (pinfunction "87.PD6_P$87") (pintype "bidirectional"))
    )
    (net (code "94") (name "SPI3_SCLK") (class "Default")
      (node (ref "Q3") (pin "2") (pinfunction "S_2") (pintype "bidirectional"))
      (node (ref "R22") (pin "1") (pinfunction "1_1") (pintype "passive"))
      (node (ref "TP43") (pin "P$1") (pinfunction "1_P$1") (pintype "bidirectional"))
      (node (ref "U3") (pin "P$78") (pinfunction "78.PC10_P$78") (pintype "bidirectional"))
    )
    (net (code "95") (name "SPI4_MOSI") (class "Default")
      (node (ref "Q8") (pin "2") (pinfunction "S_2") (pintype "bidirectional"))
      (node (ref "R31") (pin "1") (pinfunction "1_1") (pintype "passive"))
      (node (ref "TP36") (pin "P$1") (pinfunction "1_P$1") (pintype "bidirectional"))
      (node (ref "U3") (pin "P$5") (pinfunction "5.PE6_P$5") (pintype "bidirectional"))
    )
    (net (code "96") (name "SPI4_SCLK") (class "Default")
      (node (ref "Q4") (pin "2") (pinfunction "S_2") (pintype "bidirectional"))
      (node (ref "R23") (pin "1") (pinfunction "1_1") (pintype "passive"))
      (node (ref "TP44") (pin "P$1") (pinfunction "1_P$1") (pintype "bidirectional"))
      (node (ref "U3") (pin "P$42") (pinfunction "42.PE12_P$42") (pintype "bidirectional"))
    )
    (net (code "97") (name "SPI6_MISO") (class "Default")
      (node (ref "TP8") (pin "P$1") (pinfunction "1_P$1") (pintype "bidirectional"))
      (node (ref "U1") (pin "31") (pinfunction "MISO_V/IO19_31") (pintype "bidirectional"))
      (node (ref "U3") (pin "P$90") (pinfunction "90.PB4_P$90") (pintype "bidirectional"))
    )
    (net (code "98") (name "SPI6_MOSI") (class "Default")
      (node (ref "TP7") (pin "P$1") (pinfunction "1_P$1") (pintype "bidirectional"))
      (node (ref "U1") (pin "37") (pinfunction "MOSI_V/IO23_37") (pintype "bidirectional"))
      (node (ref "U3") (pin "P$31") (pinfunction "31.PA7_P$31") (pintype "bidirectional"))
    )
    (net (code "99") (name "SPI6_SCLK") (class "Default")
      (node (ref "TP9") (pin "P$1") (pinfunction "1_P$1") (pintype "bidirectional"))
      (node (ref "U1") (pin "30") (pinfunction "SCK_V/IO18_30") (pintype "bidirectional"))
      (node (ref "U3") (pin "P$29") (pinfunction "29.PA5_P$29") (pintype "bidirectional"))
    )
    (net (code "100") (name "STM_USB_DM") (class "Default")
      (node (ref "J2") (pin "D-") (pinfunction "D-_D-") (pintype "bidirectional"))
      (node (ref "U3") (pin "P$70") (pinfunction "70.PA11_P$70") (pintype "bidirectional"))
    )
    (net (code "101") (name "STM_USB_DP") (class "Default")
      (node (ref "J2") (pin "D+") (pinfunction "D+_D+") (pintype "bidirectional"))
      (node (ref "U3") (pin "P$71") (pinfunction "71.PA12_P$71") (pintype "bidirectional"))
    )
    (net (code "102") (name "SWCLK") (class "Default")
      (node (ref "R14") (pin "2") (pinfunction "2_2") (pintype "passive"))
      (node (ref "R17") (pin "1") (pinfunction "1_1") (pintype "passive"))
      (node (ref "TP68") (pin "P$1") (pinfunction "1_P$1") (pintype "bidirectional"))
      (node (ref "U3") (pin "P$76") (pinfunction "76.PA14_P$76") (pintype "bidirectional"))
    )
    (net (code "103") (name "SWDIO") (class "Default")
      (node (ref "R13") (pin "2") (pinfunction "2_2") (pintype "passive"))
      (node (ref "R18") (pin "1") (pinfunction "1_1") (pintype "passive"))
      (node (ref "TP78") (pin "P$1") (pinfunction "1_P$1") (pintype "bidirectional"))
      (node (ref "U3") (pin "P$72") (pinfunction "72.PA13_P$72") (pintype "bidirectional"))
    )
    (net (code "104") (name "UART4_RX") (class "Default")
      (node (ref "U1") (pin "28") (pinfunction "IO17_28") (pintype "bidirectional"))
      (node (ref "U3") (pin "P$23") (pinfunction "23.PA1_P$23") (pintype "bidirectional"))
    )
    (net (code "105") (name "UART4_TX") (class "Default")
      (node (ref "U1") (pin "27") (pinfunction "IO16_27") (pintype "bidirectional"))
      (node (ref "U3") (pin "P$22") (pinfunction "22.PA0_P$22") (pintype "bidirectional"))
    )
    (net (code "106") (name "UART5_RX") (class "Default")
      (node (ref "U3") (pin "P$51") (pinfunction "51.PB12_P$51") (pintype "bidirectional"))
    )
    (net (code "107") (name "UART5_TX") (class "Default")
      (node (ref "U3") (pin "P$80") (pinfunction "80.PC12_P$80") (pintype "bidirectional"))
    )
    (net (code "110") (name "UART8_RX") (class "Default")
      (node (ref "U3") (pin "P$97") (pinfunction "97.PE0_P$97") (pintype "bidirectional"))
    )
    (net (code "111") (name "UART8_TX") (class "Default")
      (node (ref "U3") (pin "P$98") (pinfunction "98.PE1_P$98") (pintype "bidirectional"))
    )
    (net (code "112") (name "ULED1") (class "Default")
      (node (ref "R11") (pin "1") (pinfunction "1_1") (pintype "passive"))
      (node (ref "U3") (pin "P$7") (pinfunction "7.PC13_P$7") (pintype "bidirectional"))
    )
    (net (code "113") (name "ULED2") (class "Default")
      (node (ref "R12") (pin "1") (pinfunction "1_1") (pintype "passive"))
      (node (ref "U3") (pin "P$8") (pinfunction "8.PC14_P$8") (pintype "bidirectional"))
    )
    (net (code "114") (name "US1") (class "Default")
      (node (ref "M1") (pin "P$3") (pinfunction "3_P$3") (pintype "passive"))
      (node (ref "M2") (pin "P$3") (pinfunction "3_P$3") (pintype "bidirectional"))
      (node (ref "R20") (pin "2") (pinfunction "2_2") (pintype "passive"))
      (node (ref "S5") (pin "1") (pinfunction "1_1") (pintype "passive"))
      (node (ref "S5") (pin "2") (pinfunction "1_2") (pintype "passive"))
      (node (ref "U3") (pin "P$85") (pinfunction "85.PD4_P$85") (pintype "bidirectional"))
    )
    (net (code "115") (name "US2") (class "Default")
      (node (ref "M1") (pin "P$1") (pinfunction "1_P$1") (pintype "passive"))
      (node (ref "M2") (pin "P$1") (pinfunction "1_P$1") (pintype "bidirectional"))
      (node (ref "R16") (pin "2") (pinfunction "2_2") (pintype "passive"))
      (node (ref "S3") (pin "1") (pinfunction "1_1") (pintype "passive"))
      (node (ref "S3") (pin "2") (pinfunction "1_2") (pintype "passive"))
      (node (ref "U3") (pin "P$86") (pinfunction "86.PD5_P$86") (pintype "bidirectional"))
    )
    (net (code "116") (name "USART1_RX") (class "Default")
      (node (ref "Q16") (pin "2") (pinfunction "S_2") (pintype "bidirectional"))
      (node (ref "R47") (pin "1") (pinfunction "1_1") (pintype "passive"))
      (node (ref "R55") (pin "1") (pinfunction "1_1") (pintype "passive"))
      (node (ref "TP58") (pin "P$1") (pinfunction "1_P$1") (pintype "bidirectional"))
      (node (ref "U3") (pin "P$54") (pinfunction "54.PB15_P$54") (pintype "bidirectional"))
    )
    (net (code "117") (name "USART1_RX_VOUT") (class "Default")
      (node (ref "M13") (pin "P$1") (pinfunction "1_P$1") (pintype "bidirectional"))
      (node (ref "M17") (pin "P$1") (pinfunction "1_P$1") (pintype "passive"))
      (node (ref "Q16") (pin "3") (pinfunction "D_3") (pintype "bidirectional"))
      (node (ref "R51") (pin "1") (pinfunction "1_1") (pintype "passive"))
    )
    (net (code "118") (name "USART1_TX") (class "Default")
      (node (ref "Q12") (pin "2") (pinfunction "S_2") (pintype "bidirectional"))
      (node (ref "R39") (pin "1") (pinfunction "1_1") (pintype "passive"))
      (node (ref "R53") (pin "1") (pinfunction "1_1") (pintype "passive"))
      (node (ref "TP57") (pin "P$1") (pinfunction "1_P$1") (pintype "bidirectional"))
      (node (ref "U3") (pin "P$53") (pinfunction "53.PB14_P$53") (pintype "bidirectional"))
    )
    (net (code "119") (name "USART1_TX_VOUT") (class "Default")
      (node (ref "M13") (pin "P$2") (pinfunction "2_P$2") (pintype "bidirectional"))
      (node (ref "M17") (pin "P$2") (pinfunction "2_P$2") (pintype "passive"))
      (node (ref "Q12") (pin "3") (pinfunction "D_3") (pintype "bidirectional"))
      (node (ref "R43") (pin "1") (pinfunction "1_1") (pintype "passive"))
    )
    (net (code "120") (name "USART1_VOUT") (class "Default")
      (node (ref "JP7") (pin "2") (pinfunction "2_2") (pintype "passive"))
      (node (ref "M13") (pin "P$3") (pinfunction "3_P$3") (pintype "bidirectional"))
      (node (ref "M17") (pin "P$3") (pinfunction "3_P$3") (pintype "passive"))
      (node (ref "R43") (pin "2") (pinfunction "2_2") (pintype "passive"))
      (node (ref "R51") (pin "2") (pinfunction "2_2") (pintype "passive"))
    )
    (net (code "121") (name "USB_OTG_FS_ID") (class "Default")
      (node (ref "J2") (pin "ID") (pinfunction "ID_ID") (pintype "bidirectional"))
      (node (ref "U3") (pin "P$69") (pinfunction "69.PA10_P$69") (pintype "bidirectional"))
    )
    (net (code "122") (name "USB_OTG_FS_SOF") (class "Default")
      (node (ref "U3") (pin "P$67") (pinfunction "67.PA8_P$67") (pintype "bidirectional"))
    )
    (net (code "123") (name "VOVP") (class "Default")
      (node (ref "D10") (pin "C") (pinfunction "C_C") (pintype "passive"))
      (node (ref "F1") (pin "2") (pinfunction "2_2") (pintype "bidirectional"))
      (node (ref "JP11") (pin "2") (pinfunction "2_2") (pintype "passive"))
      (node (ref "Q23") (pin "3") (pinfunction "D_3") (pintype "bidirectional"))
      (node (ref "TP48") (pin "P$1") (pinfunction "1_P$1") (pintype "bidirectional"))
    )
    (net (code "124") (name "VRAW") (class "Default")
      (node (ref "M22") (pin "P$2") (pinfunction "2_P$2") (pintype "passive"))
      (node (ref "M23") (pin "P$3") (pinfunction "2_P$3") (pintype "bidirectional"))
      (node (ref "Q22") (pin "3") (pinfunction "D_3") (pintype "bidirectional"))
    )
    (net (code "125") (name "VRPP") (class "Default")
      (node (ref "F1") (pin "1") (pinfunction "1_1") (pintype "bidirectional"))
      (node (ref "JP11") (pin "1") (pinfunction "1_1") (pintype "passive"))
      (node (ref "Q22") (pin "2") (pinfunction "S_2") (pintype "bidirectional"))
      (node (ref "TP47") (pin "P$1") (pinfunction "1_P$1") (pintype "bidirectional"))
    )
    (net (code "126") (name "V_USB") (class "Default")
      (node (ref "D11") (pin "A") (pinfunction "A_A") (pintype "passive"))
      (node (ref "J1") (pin "VBUS") (pinfunction "VBUS_VBUS") (pintype "power_in"))
      (node (ref "J2") (pin "VBUS") (pinfunction "VBUS_VBUS") (pintype "power_in"))
      (node (ref "Q23") (pin "1") (pinfunction "G_1") (pintype "bidirectional"))
      (node (ref "R68") (pin "2") (pinfunction "2_2") (pintype "passive"))
      (node (ref "TP49") (pin "P$1") (pinfunction "1_P$1") (pintype "bidirectional"))
      (node (ref "U3") (pin "P$68") (pinfunction "68.PA9_P$68") (pintype "bidirectional"))
    )
    (net (code "127") (name "unconnected-(D2-P$5-Pad5COUT)") (class "Default")
      (node (ref "D2") (pin "5COUT") (pinfunction "P$5_5COUT") (pintype "bidirectional"))
    )
    (net (code "128") (name "unconnected-(D2-P$6-Pad6DOUT)") (class "Default")
      (node (ref "D2") (pin "6DOUT") (pinfunction "P$6_6DOUT") (pintype "bidirectional"))
    )
    (net (code "129") (name "unconnected-(J1-PadID)") (class "Default")
      (node (ref "J1") (pin "ID") (pinfunction "ID_ID") (pintype "bidirectional"))
    )
    (net (code "130") (name "unconnected-(J3-KEY-Pad7)") (class "Default")
      (node (ref "J3") (pin "7") (pinfunction "KEY_7") (pintype "bidirectional"))
    )
    (net (code "131") (name "unconnected-(J3-NC{slash}TDI-Pad8)") (class "Default")
      (node (ref "J3") (pin "8") (pinfunction "NC/TDI_8") (pintype "bidirectional"))
    )
    (net (code "132") (name "unconnected-(J3-SWO{slash}TDO-Pad6)") (class "Default")
      (node (ref "J3") (pin "6") (pinfunction "SWO/TDO_6") (pintype "bidirectional"))
    )
    (net (code "133") (name "unconnected-(M21-DAT1-PadP$8)") (class "Default")
      (node (ref "M21") (pin "P$8") (pinfunction "DAT1_P$8") (pintype "bidirectional"))
    )
    (net (code "134") (name "unconnected-(M21-DAT2-PadP$1)") (class "Default")
      (node (ref "M21") (pin "P$1") (pinfunction "DAT2_P$1") (pintype "bidirectional"))
    )
    (net (code "135") (name "unconnected-(U1-CS0_H{slash}IO15-Pad23)") (class "Default")
      (node (ref "U1") (pin "23") (pinfunction "CS0_H/IO15_23") (pintype "bidirectional"))
    )
    (net (code "136") (name "unconnected-(U1-IO4-Pad26)") (class "Default")
      (node (ref "U1") (pin "26") (pinfunction "IO4_26") (pintype "bidirectional"))
    )
    (net (code "137") (name "unconnected-(U1-IO21-Pad33)") (class "Default")
      (node (ref "U1") (pin "33") (pinfunction "IO21_33") (pintype "bidirectional"))
    )
    (net (code "138") (name "unconnected-(U1-IO22-Pad36)") (class "Default")
      (node (ref "U1") (pin "36") (pinfunction "IO22_36") (pintype "bidirectional"))
    )
    (net (code "139") (name "unconnected-(U1-IO25-Pad10)") (class "Default")
      (node (ref "U1") (pin "10") (pinfunction "IO25_10") (pintype "bidirectional"))
    )
    (net (code "140") (name "unconnected-(U1-IO26-Pad11)") (class "Default")
      (node (ref "U1") (pin "11") (pinfunction "IO26_11") (pintype "bidirectional"))
    )
    (net (code "141") (name "unconnected-(U1-IO27-Pad12)") (class "Default")
      (node (ref "U1") (pin "12") (pinfunction "IO27_12") (pintype "bidirectional"))
    )
    (net (code "142") (name "unconnected-(U1-IO34-Pad6)") (class "Default")
      (node (ref "U1") (pin "6") (pinfunction "IO34_6") (pintype "bidirectional"))
    )
    (net (code "143") (name "unconnected-(U1-IO35-Pad7)") (class "Default")
      (node (ref "U1") (pin "7") (pinfunction "IO35_7") (pintype "bidirectional"))
    )
    (net (code "144") (name "unconnected-(U1-MISO_H{slash}IO12-Pad14)") (class "Default")
      (node (ref "U1") (pin "14") (pinfunction "MISO_H/IO12_14") (pintype "bidirectional"))
    )
    (net (code "145") (name "unconnected-(U1-NC-Pad32)") (class "Default")
      (node (ref "U1") (pin "32") (pinfunction "NC_32") (pintype "bidirectional"))
    )
    (net (code "146") (name "unconnected-(U1-SCK{slash}IO6-Pad20)") (class "Default")
      (node (ref "U1") (pin "20") (pinfunction "SCK/IO6_20") (pintype "bidirectional"))
    )
    (net (code "147") (name "unconnected-(U1-SCS{slash}IO11-Pad19)") (class "Default")
      (node (ref "U1") (pin "19") (pinfunction "SCS/IO11_19") (pintype "bidirectional"))
    )
    (net (code "148") (name "unconnected-(U1-SDI{slash}IO8-Pad22)") (class "Default")
      (node (ref "U1") (pin "22") (pinfunction "SDI/IO8_22") (pintype "bidirectional"))
    )
    (net (code "149") (name "unconnected-(U1-SDO{slash}IO7-Pad21)") (class "Default")
      (node (ref "U1") (pin "21") (pinfunction "SDO/IO7_21") (pintype "bidirectional"))
    )
    (net (code "150") (name "unconnected-(U1-SENSOR_VN{slash}I39-Pad5)") (class "Default")
      (node (ref "U1") (pin "5") (pinfunction "SENSOR_VN/I39_5") (pintype "bidirectional"))
    )
    (net (code "151") (name "unconnected-(U1-SENSOR_VP{slash}I36-Pad4)") (class "Default")
      (node (ref "U1") (pin "4") (pinfunction "SENSOR_VP/I36_4") (pintype "bidirectional"))
    )
    (net (code "152") (name "unconnected-(U1-SHD{slash}IO9-Pad17)") (class "Default")
      (node (ref "U1") (pin "17") (pinfunction "SHD/IO9_17") (pintype "bidirectional"))
    )
    (net (code "153") (name "unconnected-(U1-SWP{slash}IO10-Pad18)") (class "Default")
      (node (ref "U1") (pin "18") (pinfunction "SWP/IO10_18") (pintype "bidirectional"))
    )
    (net (code "154") (name "unconnected-(U1-XTAL_N{slash}IO33-Pad9)") (class "Default")
      (node (ref "U1") (pin "9") (pinfunction "XTAL_N/IO33_9") (pintype "bidirectional"))
    )
    (net (code "155") (name "unconnected-(U1-XTAL_P{slash}IO32-Pad8)") (class "Default")
      (node (ref "U1") (pin "8") (pinfunction "XTAL_P/IO32_8") (pintype "bidirectional"))
    )
    (net (code "156") (name "unconnected-(U3-17.PC2-PadP$17)") (class "Default")
      (node (ref "U3") (pin "P$17") (pinfunction "17.PC2_P$17") (pintype "bidirectional"))
    )
    (net (code "157") (name "unconnected-(U3-18.PC3-PadP$18)") (class "Default")
      (node (ref "U3") (pin "P$18") (pinfunction "18.PC3_P$18") (pintype "bidirectional"))
    )
    (net (code "158") (name "unconnected-(U3-24.PA2-PadP$24)") (class "Default")
      (node (ref "U3") (pin "P$24") (pinfunction "24.PA2_P$24") (pintype "bidirectional"))
    )
    (net (code "159") (name "unconnected-(U3-25.PA3-PadP$25)") (class "Default")
      (node (ref "U3") (pin "P$25") (pinfunction "25.PA3_P$25") (pintype "bidirectional"))
    )
    (net (code "160") (name "unconnected-(U3-28.PA4-PadP$28)") (class "Default")
      (node (ref "U3") (pin "P$28") (pinfunction "28.PA4_P$28") (pintype "bidirectional"))
    )
    (net (code "161") (name "unconnected-(U3-32.PC4-PadP$32)") (class "Default")
      (node (ref "U3") (pin "P$32") (pinfunction "32.PC4_P$32") (pintype "bidirectional"))
    )
    (net (code "162") (name "unconnected-(U3-33.PC5-PadP$33)") (class "Default")
      (node (ref "U3") (pin "P$33") (pinfunction "33.PC5_P$33") (pintype "bidirectional"))
    )
    (net (code "163") (name "unconnected-(U3-34.PB0-PadP$34)") (class "Default")
      (node (ref "U3") (pin "P$34") (pinfunction "34.PB0_P$34") (pintype "bidirectional"))
    )
    (net (code "164") (name "unconnected-(U3-35.PB1-PadP$35)") (class "Default")
      (node (ref "U3") (pin "P$35") (pinfunction "35.PB1_P$35") (pintype "bidirectional"))
    )
    (net (code "165") (name "unconnected-(U3-41.PE11-PadP$41)") (class "Default")
      (node (ref "U3") (pin "P$41") (pinfunction "41.PE11_P$41") (pintype "bidirectional"))
    )
    (net (code "166") (name "unconnected-(U3-43.PE13-PadP$43)") (class "Default")
      (node (ref "U3") (pin "P$43") (pinfunction "43.PE13_P$43") (pintype "bidirectional"))
    )
    (net (code "167") (name "unconnected-(U3-44.PE14-PadP$44)") (class "Default")
      (node (ref "U3") (pin "P$44") (pinfunction "44.PE14_P$44") (pintype "bidirectional"))
    )
    (net (code "168") (name "unconnected-(U3-45.PE15-PadP$45)") (class "Default")
      (node (ref "U3") (pin "P$45") (pinfunction "45.PE15_P$45") (pintype "bidirectional"))
    )
    (net (code "169") (name "unconnected-(U3-55.PD8-PadP$55)") (class "Default")
      (node (ref "U3") (pin "P$55") (pinfunction "55.PD8_P$55") (pintype "bidirectional"))
    )
    (net (code "170") (name "unconnected-(U3-56.PD9-PadP$56)") (class "Default")
      (node (ref "U3") (pin "P$56") (pinfunction "56.PD9_P$56") (pintype "bidirectional"))
    )
    (net (code "171") (name "unconnected-(U3-57.PD10-PadP$57)") (class "Default")
      (node (ref "U3") (pin "P$57") (pinfunction "57.PD10_P$57") (pintype "bidirectional"))
    )
    (net (code "172") (name "unconnected-(U3-61.PD14-PadP$61)") (class "Default")
      (node (ref "U3") (pin "P$61") (pinfunction "61.PD14_P$61") (pintype "bidirectional"))
    )
    (net (code "173") (name "unconnected-(U3-62.PD15-PadP$62)") (class "Default")
      (node (ref "U3") (pin "P$62") (pinfunction "62.PD15_P$62") (pintype "bidirectional"))
    )
    (net (code "174") (name "unconnected-(U3-65.PC8-PadP$65)") (class "Default")
      (node (ref "U3") (pin "P$65") (pinfunction "65.PC8_P$65") (pintype "bidirectional"))
    )
    (net (code "175") (name "unconnected-(U3-66.PC9-PadP$66)") (class "Default")
      (node (ref "U3") (pin "P$66") (pinfunction "66.PC9_P$66") (pintype "bidirectional"))
    )
    (net (code "176") (name "unconnected-(U3-77.PA15-PadP$77)") (class "Default")
      (node (ref "U3") (pin "P$77") (pinfunction "77.PA15_P$77") (pintype "bidirectional"))
    )
    (net (code "177") (name "unconnected-(U3-91.PB5-PadP$91)") (class "Default")
      (node (ref "U3") (pin "P$91") (pinfunction "91.PB5_P$91") (pintype "bidirectional"))
    )
    (net (code "178") (name "unconnected-(U3-96.PB9-PadP$96)") (class "Default")
      (node (ref "U3") (pin "P$96") (pinfunction "96.PB9_P$96") (pintype "bidirectional"))
    )
    (net (code "179") (name "unconnected-(U5-AUX_CL-Pad7)") (class "Default")
      (node (ref "U5") (pin "7") (pinfunction "AUX_CL_7") (pintype "bidirectional"))
    )
    (net (code "180") (name "unconnected-(U5-AUX_DA-Pad21)") (class "Default")
      (node (ref "U5") (pin "21") (pinfunction "AUX_DA_21") (pintype "bidirectional"))
    )
    (net (code "181") (name "unconnected-(U6-A4-Pad4)") (class "Default")
      (node (ref "U6") (pin "4") (pinfunction "A4_4") (pintype "bidirectional"))
    )
    (net (code "182") (name "unconnected-(U6-A5-Pad7)") (class "Default")
      (node (ref "U6") (pin "7") (pinfunction "A5_7") (pintype "bidirectional"))
    )
    (net (code "183") (name "unconnected-(U6-B4-Pad17)") (class "Default")
      (node (ref "U6") (pin "17") (pinfunction "B4_17") (pintype "bidirectional"))
    )
    (net (code "184") (name "unconnected-(U6-B5-Pad14)") (class "Default")
      (node (ref "U6") (pin "14") (pinfunction "B5_14") (pintype "bidirectional"))
    )
    (net (code "185") (name "unconnected-(U7-NC-Pad4)") (class "Default")
      (node (ref "U7") (pin "4") (pinfunction "NC_4") (pintype "no_connect"))
    )
    (net (code "186") (name "unconnected-(U8-R232-Pad15)") (class "Default")
      (node (ref "U8") (pin "15") (pinfunction "R232_15") (pintype "bidirectional"))
    )
    (net (code "187") (name "unconnected-(U8-~{CTS}-Pad9)") (class "Default")
      (node (ref "U8") (pin "9") (pinfunction "~{CTS}_9") (pintype "bidirectional"))
    )
    (net (code "188") (name "unconnected-(U8-~{DCD}-Pad12)") (class "Default")
      (node (ref "U8") (pin "12") (pinfunction "~{DCD}_12") (pintype "bidirectional"))
    )
    (net (code "189") (name "unconnected-(U8-~{DSR}-Pad10)") (class "Default")
      (node (ref "U8") (pin "10") (pinfunction "~{DSR}_10") (pintype "bidirectional"))
    )
    (net (code "190") (name "unconnected-(U8-~{RI}-Pad11)") (class "Default")
      (node (ref "U8") (pin "11") (pinfunction "~{RI}_11") (pintype "bidirectional"))
    )
  )
)
